# MK66MCU.net
KiCad netlist of a schematic drawn in Altium Designer
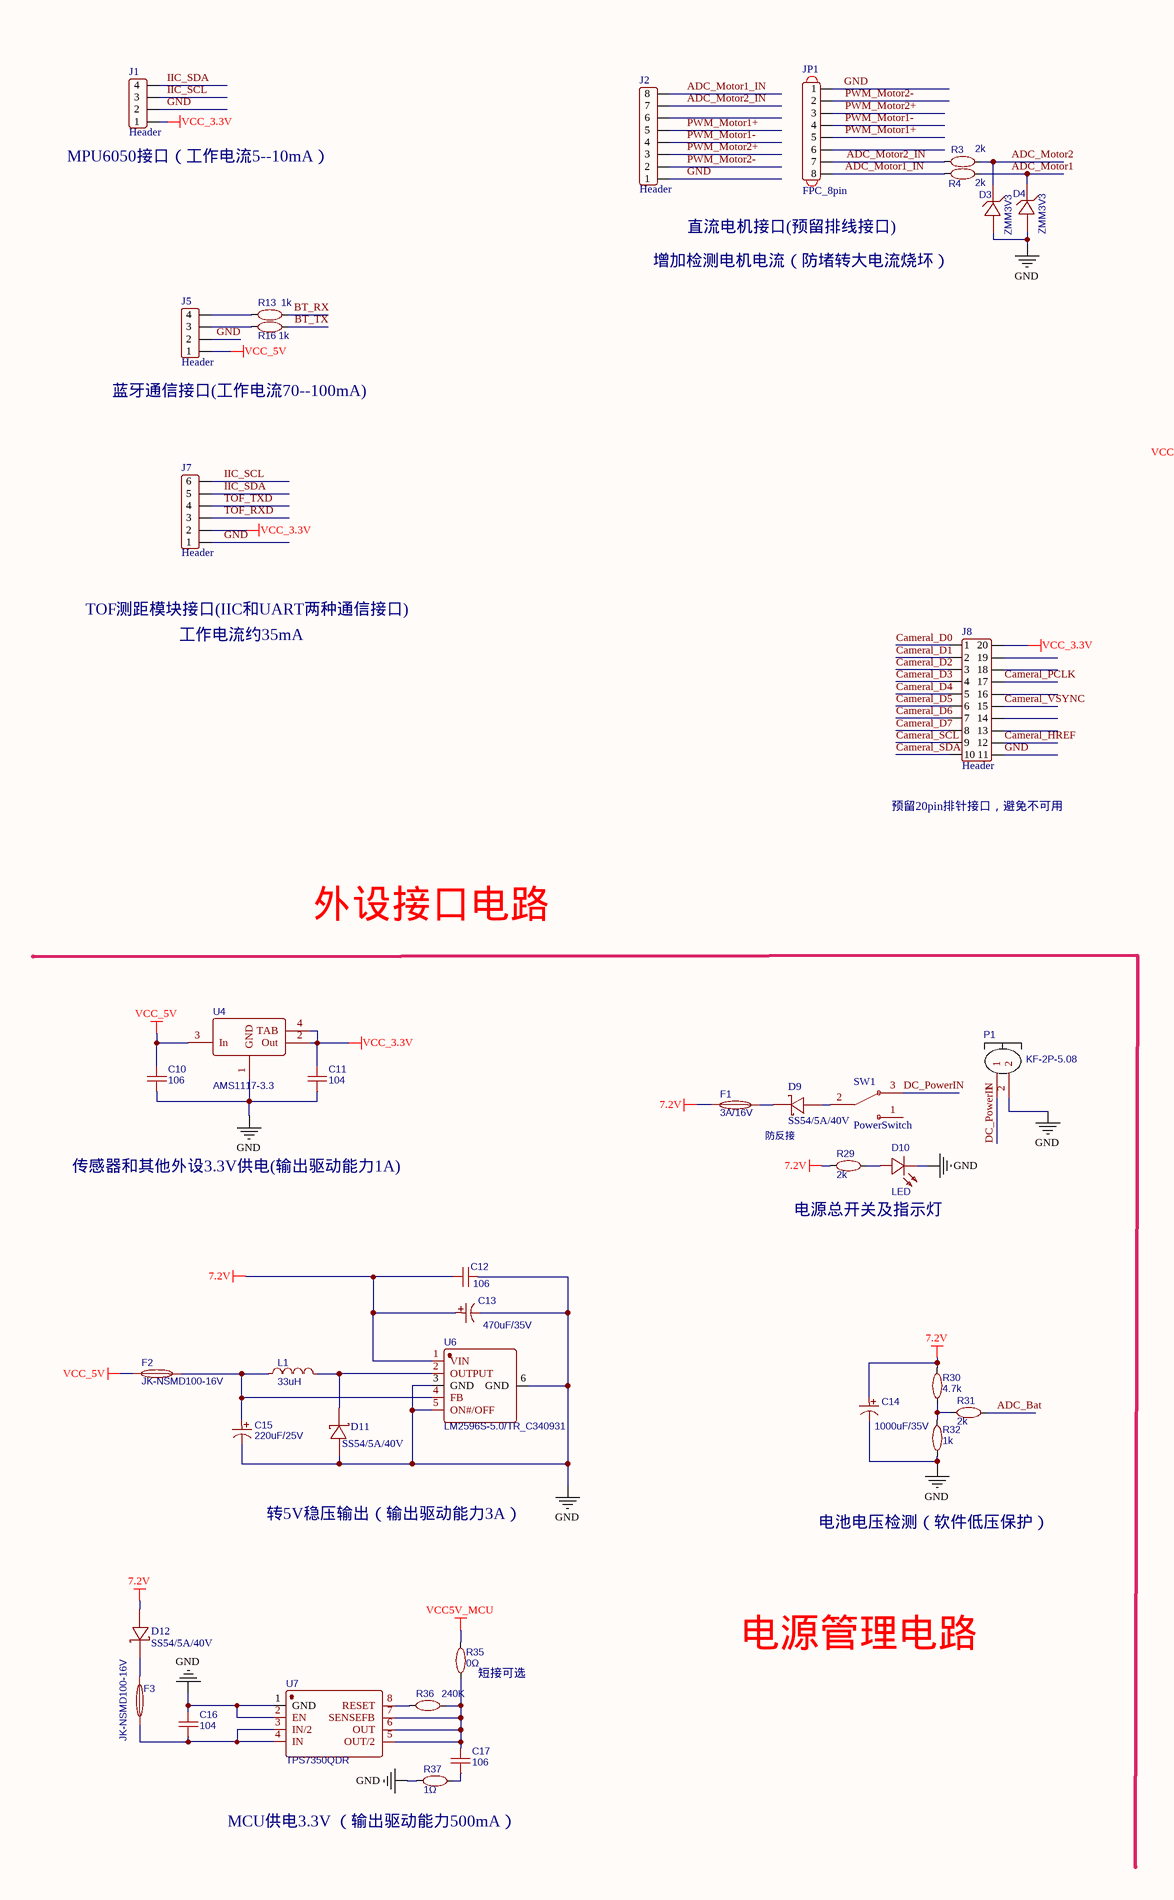
[diagram p0: MK66MCU.SchDoc, left]
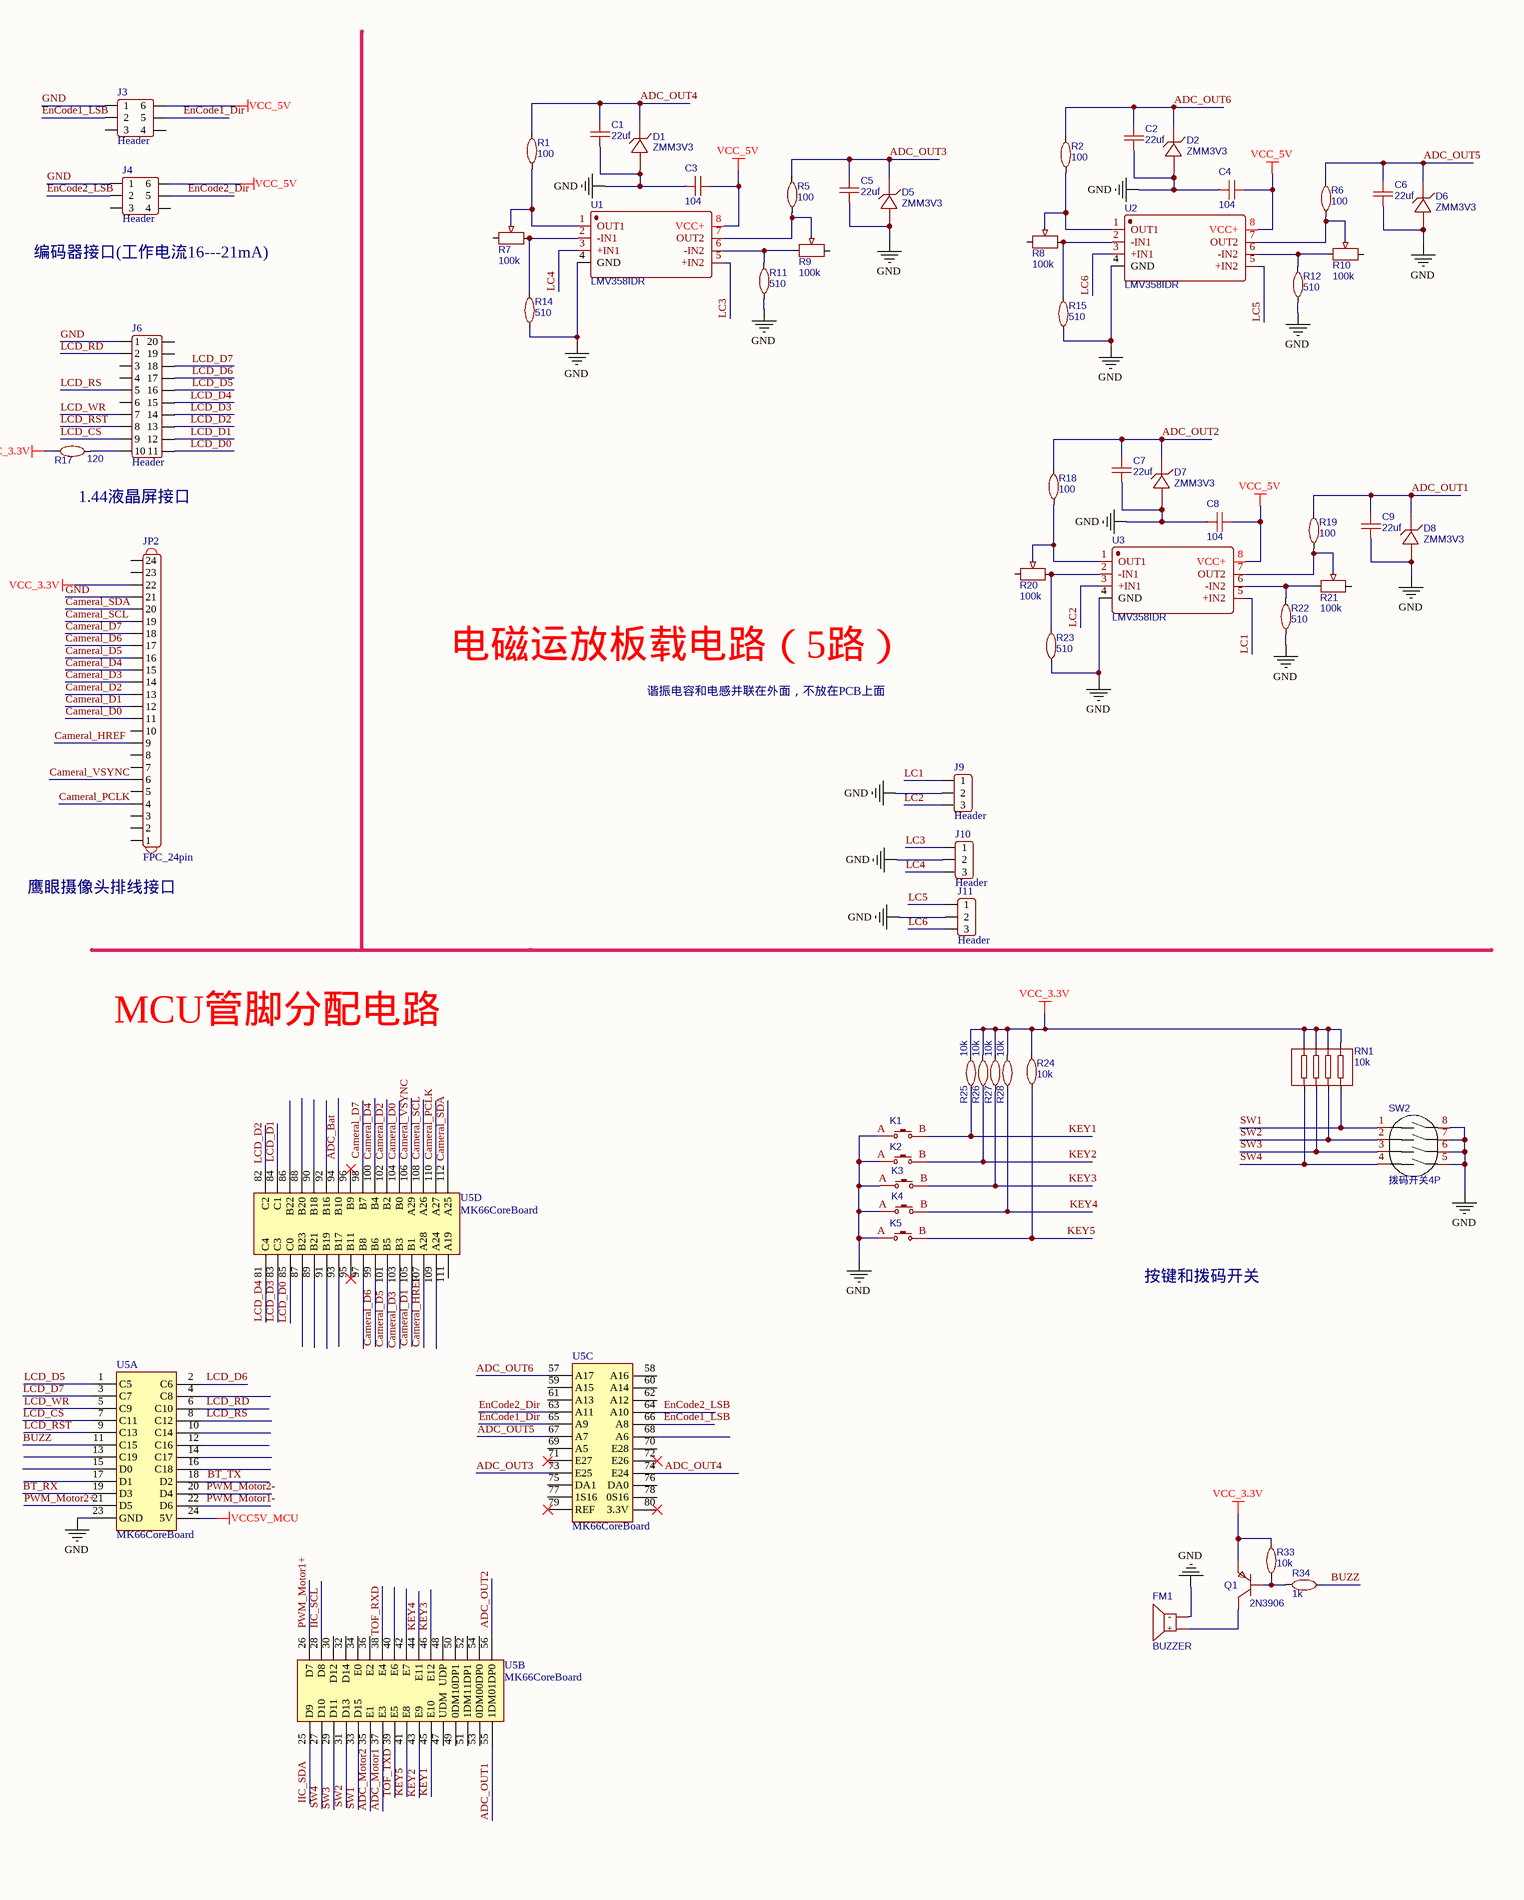
[diagram p1: MK66MCU.SchDoc, right]

(export (version "E")
  (design (tool "Eeschema 10.0.6"))
  (components
    (comp (ref "C1")
      (value "22uf")
      (footprint "CAP_0603")
      (fields
        (field (name "BOM_SUPPLIER PART") "C307348")
        (field (name "BOM_MANUFACTURER PART") "CL10B104KB8WPNC")
        (field (name "CONTRIBUTOR") "LCSC")
      )
      (libsource (lib "LTC_Library1") (part "CAP_0603"))
    )
    (comp (ref "C2")
      (value "22uf")
      (footprint "CAP_0603")
      (fields
        (field (name "BOM_SUPPLIER PART") "C307348")
        (field (name "BOM_MANUFACTURER PART") "CL10B104KB8WPNC")
        (field (name "CONTRIBUTOR") "LCSC")
      )
      (libsource (lib "LTC_Library1") (part "CAP_0603"))
    )
    (comp (ref "C3")
      (value "104")
      (footprint "CAP_0603")
      (fields
        (field (name "BOM_SUPPLIER PART") "C307348")
        (field (name "BOM_MANUFACTURER PART") "CL10B104KB8WPNC")
        (field (name "CONTRIBUTOR") "LCSC")
      )
      (libsource (lib "LTC_Library1") (part "CAP_0603"))
    )
    (comp (ref "C4")
      (value "104")
      (footprint "CAP_0603")
      (fields
        (field (name "BOM_SUPPLIER PART") "C307348")
        (field (name "BOM_MANUFACTURER PART") "CL10B104KB8WPNC")
        (field (name "CONTRIBUTOR") "LCSC")
      )
      (libsource (lib "LTC_Library1") (part "CAP_0603"))
    )
    (comp (ref "C5")
      (value "22uf")
      (footprint "CAP_0603")
      (fields
        (field (name "BOM_SUPPLIER PART") "C307348")
        (field (name "BOM_MANUFACTURER PART") "CL10B104KB8WPNC")
        (field (name "CONTRIBUTOR") "LCSC")
      )
      (libsource (lib "LTC_Library1") (part "CAP_0603"))
    )
    (comp (ref "C6")
      (value "22uf")
      (footprint "CAP_0603")
      (fields
        (field (name "BOM_SUPPLIER PART") "C307348")
        (field (name "BOM_MANUFACTURER PART") "CL10B104KB8WPNC")
        (field (name "CONTRIBUTOR") "LCSC")
      )
      (libsource (lib "LTC_Library1") (part "CAP_0603"))
    )
    (comp (ref "C7")
      (value "22uf")
      (footprint "CAP_0603")
      (fields
        (field (name "BOM_SUPPLIER PART") "C307348")
        (field (name "BOM_MANUFACTURER PART") "CL10B104KB8WPNC")
        (field (name "CONTRIBUTOR") "LCSC")
      )
      (libsource (lib "LTC_Library1") (part "CAP_0603"))
    )
    (comp (ref "C8")
      (value "104")
      (footprint "CAP_0603")
      (fields
        (field (name "BOM_SUPPLIER PART") "C307348")
        (field (name "BOM_MANUFACTURER PART") "CL10B104KB8WPNC")
        (field (name "CONTRIBUTOR") "LCSC")
      )
      (libsource (lib "LTC_Library1") (part "CAP_0603"))
    )
    (comp (ref "C9")
      (value "22uf")
      (footprint "CAP_0603")
      (fields
        (field (name "BOM_SUPPLIER PART") "C307348")
        (field (name "BOM_MANUFACTURER PART") "CL10B104KB8WPNC")
        (field (name "CONTRIBUTOR") "LCSC")
      )
      (libsource (lib "LTC_Library1") (part "CAP_0603"))
    )
    (comp (ref "C10")
      (value "106")
      (footprint "CAP_0603")
      (fields
        (field (name "BOM_SUPPLIER PART") "C307348")
        (field (name "BOM_MANUFACTURER PART") "CL10B104KB8WPNC")
        (field (name "CONTRIBUTOR") "LCSC")
      )
      (libsource (lib "LTC_Library1") (part "CAP_0603"))
    )
    (comp (ref "C11")
      (value "104")
      (footprint "CAP_0603")
      (fields
        (field (name "BOM_SUPPLIER PART") "C307348")
        (field (name "BOM_MANUFACTURER PART") "CL10B104KB8WPNC")
        (field (name "CONTRIBUTOR") "LCSC")
      )
      (libsource (lib "LTC_Library1") (part "CAP_0603"))
    )
    (comp (ref "C12")
      (value "106")
      (footprint "CAP_0603")
      (fields
        (field (name "BOM_SUPPLIER PART") "C307348")
        (field (name "BOM_MANUFACTURER PART") "CL10B104KB8WPNC")
        (field (name "CONTRIBUTOR") "LCSC")
      )
      (libsource (lib "LTC_Library1") (part "CAP_0603"))
    )
    (comp (ref "C13")
      (value "470uF/35V")
      (footprint "CAPE_SMD_F_8.4")
      (description "贴片电解电容")
      (fields
        (field (name "BOM_MANUFACTURER PART") "RVT1C221M0607")
        (field (name "BOM_SUPPLIER PART") "C72496")
      )
      (libsource (lib "") (part "CAP_E_SMD_1"))
    )
    (comp (ref "C14")
      (value "1000uF/35V")
      (footprint "CAPE_SMD_G_10.6")
      (description "贴片电解电容")
      (fields
        (field (name "BOM_MANUFACTURER PART") "RVT1C221M0607")
        (field (name "BOM_SUPPLIER PART") "C72496")
      )
      (libsource (lib "LTC_Library1") (part "CAP_E_SMD"))
    )
    (comp (ref "C15")
      (value "220uF/25V")
      (footprint "CAPE_SMD_D_6.4")
      (description "贴片电解电容")
      (fields
        (field (name "BOM_MANUFACTURER PART") "RVT1C221M0607")
        (field (name "BOM_SUPPLIER PART") "C72496")
      )
      (libsource (lib "LTC_Library1") (part "CAP_E_SMD"))
    )
    (comp (ref "C16")
      (value "104")
      (footprint "CAP_0603")
      (fields
        (field (name "BOM_SUPPLIER PART") "C307348")
        (field (name "BOM_MANUFACTURER PART") "CL10B104KB8WPNC")
        (field (name "CONTRIBUTOR") "LCSC")
      )
      (libsource (lib "LTC_Library1") (part "CAP_0603"))
    )
    (comp (ref "C17")
      (value "106")
      (footprint "CAP_0603")
      (fields
        (field (name "BOM_SUPPLIER PART") "C307348")
        (field (name "BOM_MANUFACTURER PART") "CL10B104KB8WPNC")
        (field (name "CONTRIBUTOR") "LCSC")
      )
      (libsource (lib "LTC_Library1") (part "CAP_0603"))
    )
    (comp (ref "D1")
      (value "ZMM3V3")
      (footprint "LL-34_L3.5-W1.5-RD")
      (fields (field (name "BOM_SUPPLIER PART") "C8056"))
      (libsource (lib "SmartCar_Library") (part "ZMM3V3"))
    )
    (comp (ref "D2")
      (value "ZMM3V3")
      (footprint "LL-34_L3.5-W1.5-RD")
      (fields (field (name "BOM_SUPPLIER PART") "C8056"))
      (libsource (lib "SmartCar_Library") (part "ZMM3V3"))
    )
    (comp (ref "D3")
      (value "ZMM3V3")
      (footprint "LL-34_L3.5-W1.5-RD")
      (fields (field (name "BOM_SUPPLIER PART") "C8056"))
      (libsource (lib "SmartCar_Library") (part "ZMM3V3"))
    )
    (comp (ref "D4")
      (value "ZMM3V3")
      (footprint "LL-34_L3.5-W1.5-RD")
      (fields (field (name "BOM_SUPPLIER PART") "C8056"))
      (libsource (lib "SmartCar_Library") (part "ZMM3V3"))
    )
    (comp (ref "D5")
      (value "ZMM3V3")
      (footprint "LL-34_L3.5-W1.5-RD")
      (fields (field (name "BOM_SUPPLIER PART") "C8056"))
      (libsource (lib "SmartCar_Library") (part "ZMM3V3"))
    )
    (comp (ref "D6")
      (value "ZMM3V3")
      (footprint "LL-34_L3.5-W1.5-RD")
      (fields (field (name "BOM_SUPPLIER PART") "C8056"))
      (libsource (lib "SmartCar_Library") (part "ZMM3V3"))
    )
    (comp (ref "D7")
      (value "ZMM3V3")
      (footprint "LL-34_L3.5-W1.5-RD")
      (fields (field (name "BOM_SUPPLIER PART") "C8056"))
      (libsource (lib "SmartCar_Library") (part "ZMM3V3"))
    )
    (comp (ref "D8")
      (value "ZMM3V3")
      (footprint "LL-34_L3.5-W1.5-RD")
      (fields (field (name "BOM_SUPPLIER PART") "C8056"))
      (libsource (lib "SmartCar_Library") (part "ZMM3V3"))
    )
    (comp (ref "D9")
      (value "SS54/5A/40V")
      (footprint "DO214_SMA")
      (libsource (lib "LTC_Library1") (part "SS54"))
    )
    (comp (ref "D10")
      (value "LED")
      (footprint "LED_0603_B")
      (description "发光LED")
      (fields
        (field (name "BOM_MANUFACTURER PART") "D-G080508G1")
        (field (name "BOM_SUPPLIER PART") "C107402")
        (field (name "CONTRIBUTOR") "LCSC")
      )
      (libsource (lib "LTC_Library1") (part "LED_0603"))
    )
    (comp (ref "D11")
      (value "SS54/5A/40V")
      (footprint "DO214_SMA")
      (libsource (lib "LTC_Library1") (part "SS54"))
    )
    (comp (ref "D12")
      (value "SS54/5A/40V")
      (footprint "DO214_SMA")
      (libsource (lib "LTC_Library1") (part "SS54"))
    )
    (comp (ref "F1")
      (value "3A/16V")
      (footprint "F1206")
      (fields
        (field (name "BOM_SUPPLIER PART") "C369161")
        (field (name "BOM_MANUFACTURER PART") "JK-NSMD100-16V")
        (field (name "CONTRIBUTOR") "LCSC")
      )
      (libsource (lib "SmartCar_Library") (part "JK-NSMD100-16V"))
    )
    (comp (ref "F2")
      (value "JK-NSMD100-16V")
      (footprint "F1206")
      (fields (field (name "BOM_SUPPLIER PART") "C369161") (field (name "CONTRIBUTOR") "LCSC"))
      (libsource (lib "SmartCar_Library") (part "JK-NSMD100-16V"))
    )
    (comp (ref "F3")
      (value "JK-NSMD100-16V")
      (footprint "F1206")
      (fields (field (name "BOM_SUPPLIER PART") "C369161") (field (name "CONTRIBUTOR") "LCSC"))
      (libsource (lib "SmartCar_Library") (part "JK-NSMD100-16V"))
    )
    (comp (ref "FM1")
      (value "BUZZER")
      (footprint "BUZZ-12*7.5")
      (description "蜂鸣器")
      (fields (field (name "BOM_MANUFACTURER PART") "TMB12A12") (field (name "BOM_SUPPLIER PART") "C96079"))
      (libsource (lib "LTC_Library1") (part "BUZZER"))
    )
    (comp (ref "J1")
      (value "Header")
      (footprint "Header 2.54X4")
      (libsource (lib "LTC_Library1") (part "Header 2.54_4"))
    )
    (comp (ref "J2")
      (value "Header")
      (footprint "Header 2.54X8")
      (libsource (lib "LTC_Library1") (part "Header 2.54_8"))
    )
    (comp (ref "J3")
      (value "Header")
      (footprint "Header 2.54_2X3")
      (libsource (lib "LTC_Library1") (part "Header 2.54_2X3"))
    )
    (comp (ref "J4")
      (value "Header")
      (footprint "Header 2.54_2X3")
      (libsource (lib "LTC_Library1") (part "Header 2.54_2X3"))
    )
    (comp (ref "J5")
      (value "Header")
      (footprint "Header F 2.54X4")
      (libsource (lib "LTC_Library1") (part "Header 2.54_4"))
    )
    (comp (ref "J6")
      (value "Header")
      (footprint "Header F 2.54_2x10")
      (libsource (lib "LTC_Library1") (part "Header 2.54_2X10"))
    )
    (comp (ref "J7")
      (value "Header")
      (footprint "Header 2.54X6")
      (libsource (lib "LTC_Library1") (part "Header 2.54_6"))
    )
    (comp (ref "J8")
      (value "Header")
      (footprint "Header F 2.54_2x10")
      (libsource (lib "LTC_Library1") (part "Header 2.54_2X10"))
    )
    (comp (ref "J9")
      (value "Header")
      (footprint "Header 2.54X3")
      (libsource (lib "LTC_Library1") (part "Header 2.54_3"))
    )
    (comp (ref "J10")
      (value "Header")
      (footprint "Header 2.54X3")
      (libsource (lib "LTC_Library1") (part "Header 2.54_3"))
    )
    (comp (ref "J11")
      (value "Header")
      (footprint "Header 2.54X3")
      (libsource (lib "LTC_Library1") (part "Header 2.54_3"))
    )
    (comp (ref "JP1")
      (value "FPC_8pin")
      (footprint "FPC_1.0_8P")
      (libsource (lib "LTC_Library1") (part "FPC_8pin"))
    )
    (comp (ref "JP2")
      (value "FPC_24pin")
      (footprint "FPC_0.5_24P")
      (libsource (lib "External Interface") (part "FPC_24pin"))
    )
    (comp (ref "K1")
      (value "TS-Button_2P")
      (footprint "SW_SMD_6.1*3.7")
      (description "贴片按键 3*6*2.5")
      (fields
        (field (name "BOM_SUPPLIER PART") "C455236")
        (field (name "BOM_MANUFACTURER PART") "TS-1007S-26")
        (field (name "CONTRIBUTOR") "LCSC")
      )
      (libsource (lib "LTC_Library1") (part "TS-Button_2P"))
    )
    (comp (ref "K2")
      (value "TS-Button_2P")
      (footprint "SW_SMD_6.1*3.7")
      (description "贴片按键 3*6*2.5")
      (fields
        (field (name "BOM_SUPPLIER PART") "C455236")
        (field (name "BOM_MANUFACTURER PART") "TS-1007S-26")
        (field (name "CONTRIBUTOR") "LCSC")
      )
      (libsource (lib "LTC_Library1") (part "TS-Button_2P"))
    )
    (comp (ref "K3")
      (value "TS-Button_2P")
      (footprint "SW_SMD_6.1*3.7")
      (description "贴片按键 3*6*2.5")
      (fields
        (field (name "BOM_SUPPLIER PART") "C455236")
        (field (name "BOM_MANUFACTURER PART") "TS-1007S-26")
        (field (name "CONTRIBUTOR") "LCSC")
      )
      (libsource (lib "LTC_Library1") (part "TS-Button_2P"))
    )
    (comp (ref "K4")
      (value "TS-Button_2P")
      (footprint "SW_SMD_6.1*3.7")
      (description "贴片按键 3*6*2.5")
      (fields
        (field (name "BOM_SUPPLIER PART") "C455236")
        (field (name "BOM_MANUFACTURER PART") "TS-1007S-26")
        (field (name "CONTRIBUTOR") "LCSC")
      )
      (libsource (lib "LTC_Library1") (part "TS-Button_2P"))
    )
    (comp (ref "K5")
      (value "TS-Button_2P")
      (footprint "SW_SMD_6.1*3.7")
      (description "贴片按键 3*6*2.5")
      (fields
        (field (name "BOM_SUPPLIER PART") "C455236")
        (field (name "BOM_MANUFACTURER PART") "TS-1007S-26")
        (field (name "CONTRIBUTOR") "LCSC")
      )
      (libsource (lib "LTC_Library1") (part "TS-Button_2P"))
    )
    (comp (ref "L1")
      (value "33uH")
      (footprint "IND-SMD_L8.0-W8.0")
      (fields
        (field (name "BOM_SUPPLIER PART") "C295130")
        (field (name "BOM_MANUFACTURER PART") "NLV25T-330J-EF")
        (field (name "CONTRIBUTOR") "LCSC")
      )
      (libsource (lib "SmartCar_Library") (part "Inductor"))
    )
    (comp (ref "P1")
      (value "KF-2P-5.08")
      (footprint "KF_2P-5.08")
      (description "端子2P")
      (fields
        (field (name "BOM_MANUFACTURER PART") "WJ500H-5.08-2P")
        (field (name "BOM_SUPPLIER PART") "C8478")
      )
      (libsource (lib "LTC_Library1") (part "KF-2P-5.08"))
    )
    (comp (ref "Q1")
      (value "2N3906")
      (footprint "TO_92A")
      (description "三极管PNP")
      (fields (field (name "BOM_SUPPLIER PART") "C305396") (field (name "CONTRIBUTOR") "LCSC"))
      (libsource (lib "LTC_Library1") (part "2N3906"))
    )
    (comp (ref "R1")
      (value "100")
      (footprint "RES_0603")
      (fields
        (field (name "BOM_MANUFACTURER PART") "RC0402JR-07100KL")
        (field (name "BOM_SUPPLIER PART") "C106234")
      )
      (libsource (lib "LTC_Library1") (part "RES_0603"))
    )
    (comp (ref "R2")
      (value "100")
      (footprint "RES_0603")
      (fields
        (field (name "BOM_MANUFACTURER PART") "RC0402JR-07100KL")
        (field (name "BOM_SUPPLIER PART") "C106234")
      )
      (libsource (lib "LTC_Library1") (part "RES_0603"))
    )
    (comp (ref "R3")
      (value "2k")
      (footprint "RES_0603")
      (fields
        (field (name "BOM_MANUFACTURER PART") "RC0402JR-07100KL")
        (field (name "BOM_SUPPLIER PART") "C106234")
      )
      (libsource (lib "LTC_Library1") (part "RES_0603"))
    )
    (comp (ref "R4")
      (value "2k")
      (footprint "RES_0603")
      (fields
        (field (name "BOM_MANUFACTURER PART") "RC0402JR-07100KL")
        (field (name "BOM_SUPPLIER PART") "C106234")
      )
      (libsource (lib "LTC_Library1") (part "RES_0603"))
    )
    (comp (ref "R5")
      (value "100")
      (footprint "RES_0603")
      (fields
        (field (name "BOM_MANUFACTURER PART") "RC0402JR-07100KL")
        (field (name "BOM_SUPPLIER PART") "C106234")
      )
      (libsource (lib "LTC_Library1") (part "RES_0603"))
    )
    (comp (ref "R6")
      (value "100")
      (footprint "RES_0603")
      (fields
        (field (name "BOM_MANUFACTURER PART") "RC0402JR-07100KL")
        (field (name "BOM_SUPPLIER PART") "C106234")
      )
      (libsource (lib "LTC_Library1") (part "RES_0603"))
    )
    (comp (ref "R7")
      (value "100k")
      (footprint "RES_POT-3296W")
      (description "可调电阻3296W")
      (fields
        (field (name "BOM_SUPPLIER PART") "C118963")
        (field (name "BOM_MANUFACTURER PART") "3296W-1-104")
        (field (name "CONTRIBUTOR") "LCSC")
      )
      (libsource (lib "LTC_Library1") (part "RES_POT-3296W"))
    )
    (comp (ref "R8")
      (value "100k")
      (footprint "RES_POT-3296W")
      (description "可调电阻3296W")
      (fields
        (field (name "BOM_SUPPLIER PART") "C118963")
        (field (name "BOM_MANUFACTURER PART") "3296W-1-104")
        (field (name "CONTRIBUTOR") "LCSC")
      )
      (libsource (lib "LTC_Library1") (part "RES_POT-3296W"))
    )
    (comp (ref "R9")
      (value "100k")
      (footprint "RES_POT-3296W")
      (description "可调电阻3296W")
      (fields
        (field (name "BOM_SUPPLIER PART") "C118963")
        (field (name "BOM_MANUFACTURER PART") "3296W-1-104")
        (field (name "CONTRIBUTOR") "LCSC")
      )
      (libsource (lib "LTC_Library1") (part "RES_POT-3296W"))
    )
    (comp (ref "R10")
      (value "100k")
      (footprint "RES_POT-3296W")
      (description "可调电阻3296W")
      (fields
        (field (name "BOM_SUPPLIER PART") "C118963")
        (field (name "BOM_MANUFACTURER PART") "3296W-1-104")
        (field (name "CONTRIBUTOR") "LCSC")
      )
      (libsource (lib "LTC_Library1") (part "RES_POT-3296W"))
    )
    (comp (ref "R11")
      (value "510")
      (footprint "RES_0603")
      (fields
        (field (name "BOM_MANUFACTURER PART") "RC0402JR-07100KL")
        (field (name "BOM_SUPPLIER PART") "C106234")
      )
      (libsource (lib "LTC_Library1") (part "RES_0603"))
    )
    (comp (ref "R12")
      (value "510")
      (footprint "RES_0603")
      (fields
        (field (name "BOM_MANUFACTURER PART") "RC0402JR-07100KL")
        (field (name "BOM_SUPPLIER PART") "C106234")
      )
      (libsource (lib "LTC_Library1") (part "RES_0603"))
    )
    (comp (ref "R13")
      (value "1k")
      (footprint "RES_0603")
      (fields
        (field (name "BOM_MANUFACTURER PART") "RC0402JR-07100KL")
        (field (name "BOM_SUPPLIER PART") "C106234")
      )
      (libsource (lib "LTC_Library1") (part "RES_0603"))
    )
    (comp (ref "R14")
      (value "510")
      (footprint "RES_0603")
      (fields
        (field (name "BOM_MANUFACTURER PART") "RC0402JR-07100KL")
        (field (name "BOM_SUPPLIER PART") "C106234")
      )
      (libsource (lib "LTC_Library1") (part "RES_0603"))
    )
    (comp (ref "R15")
      (value "510")
      (footprint "RES_0603")
      (fields
        (field (name "BOM_MANUFACTURER PART") "RC0402JR-07100KL")
        (field (name "BOM_SUPPLIER PART") "C106234")
      )
      (libsource (lib "LTC_Library1") (part "RES_0603"))
    )
    (comp (ref "R16")
      (value "1k")
      (footprint "RES_0603")
      (fields
        (field (name "BOM_MANUFACTURER PART") "RC0402JR-07100KL")
        (field (name "BOM_SUPPLIER PART") "C106234")
      )
      (libsource (lib "LTC_Library1") (part "RES_0603"))
    )
    (comp (ref "R17")
      (value "120")
      (footprint "RES_0603")
      (fields
        (field (name "BOM_MANUFACTURER PART") "RC0402JR-07100KL")
        (field (name "BOM_SUPPLIER PART") "C106234")
      )
      (libsource (lib "LTC_Library1") (part "RES_0603"))
    )
    (comp (ref "R18")
      (value "100")
      (footprint "RES_0603")
      (fields
        (field (name "BOM_MANUFACTURER PART") "RC0402JR-07100KL")
        (field (name "BOM_SUPPLIER PART") "C106234")
      )
      (libsource (lib "LTC_Library1") (part "RES_0603"))
    )
    (comp (ref "R19")
      (value "100")
      (footprint "RES_0603")
      (fields
        (field (name "BOM_MANUFACTURER PART") "RC0402JR-07100KL")
        (field (name "BOM_SUPPLIER PART") "C106234")
      )
      (libsource (lib "LTC_Library1") (part "RES_0603"))
    )
    (comp (ref "R20")
      (value "100k")
      (footprint "RES_POT-3296W")
      (description "可调电阻3296W")
      (fields
        (field (name "BOM_SUPPLIER PART") "C118963")
        (field (name "BOM_MANUFACTURER PART") "3296W-1-104")
        (field (name "CONTRIBUTOR") "LCSC")
      )
      (libsource (lib "LTC_Library1") (part "RES_POT-3296W"))
    )
    (comp (ref "R21")
      (value "100k")
      (footprint "RES_POT-3296W")
      (description "可调电阻3296W")
      (fields
        (field (name "BOM_SUPPLIER PART") "C118963")
        (field (name "BOM_MANUFACTURER PART") "3296W-1-104")
        (field (name "CONTRIBUTOR") "LCSC")
      )
      (libsource (lib "LTC_Library1") (part "RES_POT-3296W"))
    )
    (comp (ref "R22")
      (value "510")
      (footprint "RES_0603")
      (fields
        (field (name "BOM_MANUFACTURER PART") "RC0402JR-07100KL")
        (field (name "BOM_SUPPLIER PART") "C106234")
      )
      (libsource (lib "LTC_Library1") (part "RES_0603"))
    )
    (comp (ref "R23")
      (value "510")
      (footprint "RES_0603")
      (fields
        (field (name "BOM_MANUFACTURER PART") "RC0402JR-07100KL")
        (field (name "BOM_SUPPLIER PART") "C106234")
      )
      (libsource (lib "LTC_Library1") (part "RES_0603"))
    )
    (comp (ref "R24")
      (value "10k")
      (footprint "RES_0603")
      (fields
        (field (name "BOM_MANUFACTURER PART") "RC0402JR-07100KL")
        (field (name "BOM_SUPPLIER PART") "C106234")
      )
      (libsource (lib "LTC_Library1") (part "RES_0603"))
    )
    (comp (ref "R25")
      (value "10k")
      (footprint "RES_0603")
      (fields
        (field (name "BOM_MANUFACTURER PART") "RC0402JR-07100KL")
        (field (name "BOM_SUPPLIER PART") "C106234")
      )
      (libsource (lib "LTC_Library1") (part "RES_0603"))
    )
    (comp (ref "R26")
      (value "10k")
      (footprint "RES_0603")
      (fields
        (field (name "BOM_MANUFACTURER PART") "RC0402JR-07100KL")
        (field (name "BOM_SUPPLIER PART") "C106234")
      )
      (libsource (lib "LTC_Library1") (part "RES_0603"))
    )
    (comp (ref "R27")
      (value "10k")
      (footprint "RES_0603")
      (fields
        (field (name "BOM_MANUFACTURER PART") "RC0402JR-07100KL")
        (field (name "BOM_SUPPLIER PART") "C106234")
      )
      (libsource (lib "LTC_Library1") (part "RES_0603"))
    )
    (comp (ref "R28")
      (value "10k")
      (footprint "RES_0603")
      (fields
        (field (name "BOM_MANUFACTURER PART") "RC0402JR-07100KL")
        (field (name "BOM_SUPPLIER PART") "C106234")
      )
      (libsource (lib "LTC_Library1") (part "RES_0603"))
    )
    (comp (ref "R29")
      (value "2k")
      (footprint "RES_0603")
      (fields
        (field (name "BOM_MANUFACTURER PART") "RC0402JR-07100KL")
        (field (name "BOM_SUPPLIER PART") "C106234")
      )
      (libsource (lib "LTC_Library1") (part "RES_0603"))
    )
    (comp (ref "R30")
      (value "4.7k")
      (footprint "RES_0603")
      (fields
        (field (name "BOM_MANUFACTURER PART") "RC0402JR-07100KL")
        (field (name "BOM_SUPPLIER PART") "C106234")
      )
      (libsource (lib "LTC_Library1") (part "RES_0603"))
    )
    (comp (ref "R31")
      (value "2k")
      (footprint "RES_0603")
      (fields
        (field (name "BOM_MANUFACTURER PART") "RC0402JR-07100KL")
        (field (name "BOM_SUPPLIER PART") "C106234")
      )
      (libsource (lib "LTC_Library1") (part "RES_0603"))
    )
    (comp (ref "R32")
      (value "1k")
      (footprint "RES_0603")
      (fields
        (field (name "BOM_MANUFACTURER PART") "RC0402JR-07100KL")
        (field (name "BOM_SUPPLIER PART") "C106234")
      )
      (libsource (lib "LTC_Library1") (part "RES_0603"))
    )
    (comp (ref "R33")
      (value "10k")
      (footprint "RES_0603")
      (fields
        (field (name "BOM_MANUFACTURER PART") "RC0402JR-07100KL")
        (field (name "BOM_SUPPLIER PART") "C106234")
      )
      (libsource (lib "LTC_Library1") (part "RES_0603"))
    )
    (comp (ref "R34")
      (value "1k")
      (footprint "RES_0603")
      (fields
        (field (name "BOM_MANUFACTURER PART") "RC0402JR-07100KL")
        (field (name "BOM_SUPPLIER PART") "C106234")
      )
      (libsource (lib "LTC_Library1") (part "RES_0603"))
    )
    (comp (ref "R35")
      (value "0Ω")
      (footprint "RES_0603")
      (fields
        (field (name "BOM_MANUFACTURER PART") "RC0402JR-07100KL")
        (field (name "BOM_SUPPLIER PART") "C106234")
      )
      (libsource (lib "LTC_Library1") (part "RES_0603"))
    )
    (comp (ref "R36")
      (value "240K")
      (footprint "RES_0603")
      (fields
        (field (name "BOM_MANUFACTURER PART") "RC0402JR-07100KL")
        (field (name "BOM_SUPPLIER PART") "C106234")
      )
      (libsource (lib "LTC_Library1") (part "RES_0603"))
    )
    (comp (ref "R37")
      (value "1Ω")
      (footprint "RES_0603")
      (fields
        (field (name "BOM_MANUFACTURER PART") "RC0402JR-07100KL")
        (field (name "BOM_SUPPLIER PART") "C106234")
      )
      (libsource (lib "LTC_Library1") (part "RES_0603"))
    )
    (comp (ref "RN1")
      (value "10k")
      (footprint "RES-ARRAY-SMD_0603-8P-L3.2-W1.6-BL")
      (fields
        (field (name "BOM_MANUFACTURER PART") "YC164-JR-0710KL")
        (field (name "BOM_SUPPLIER PART") "C107374")
      )
      (libsource (lib "SmartCar_Library") (part "RESW4"))
    )
    (comp (ref "SW1")
      (value "PowerSwitch")
      (footprint "SW-TH_K3-1260D-K1")
      (libsource (lib "SmartCar_Library") (part "PowerSwitch"))
    )
    (comp (ref "SW2")
      (value "拨码开关4P")
      (footprint "VDG/S-04HG-R")
      (description "DIP_4PX2*2.54")
      (fields
        (field (name "BOM_MANUFACTURER PART") "VDG/S-04HG-R")
        (field (name "BOM_SUPPLIER PART") "C15781")
      )
      (libsource (lib "LTC_Library1") (part "拨码开关4P"))
    )
    (comp (ref "U1")
      (value "LMV358IDR")
      (footprint "SOIC-8_150MIL")
      (fields (field (name "BOM_SUPPLIER PART") "C63813"))
      (libsource (lib "LTC_Library1") (part "LMV358IDR"))
    )
    (comp (ref "U2")
      (value "LMV358IDR")
      (footprint "SOIC-8_150MIL")
      (fields (field (name "BOM_SUPPLIER PART") "C63813"))
      (libsource (lib "LTC_Library1") (part "LMV358IDR"))
    )
    (comp (ref "U3")
      (value "LMV358IDR")
      (footprint "SOIC-8_150MIL")
      (fields (field (name "BOM_SUPPLIER PART") "C63813"))
      (libsource (lib "LTC_Library1") (part "LMV358IDR"))
    )
    (comp (ref "U4")
      (value "AMS1117-3.3")
      (footprint "SOT-223_3")
      (fields (field (name "BOM_SUPPLIER PART") "C165482") (field (name "CONTRIBUTOR") "LCSC"))
      (libsource (lib "LTC_Library1") (part "AMS1117-3.3"))
    )
    (comp (ref "U5")
      (value "MK66CoreBoard")
      (footprint "MK66_MCU")
      (libsource (lib "") (part "MK66CoreBoard_1"))
    )
    (comp (ref "U6")
      (value "LM2596S-5.0/TR_C340931")
      (footprint "TO-263_5")
      (fields
        (field (name "BOM_SUPPLIER PART") "C340931")
        (field (name "BOM_MANUFACTURER PART") "LM2596S-5.0/TR")
        (field (name "CONTRIBUTOR") "LCSC")
      )
      (libsource (lib "LTC_Library1") (part "LM2596S-5.0/TR_C340931"))
    )
    (comp (ref "U7")
      (value "TPS7350QDR")
      (footprint "SOIC-8_150MIL")
      (fields (field (name "BOM_MANUFACTURER PART") "TPS7333QDR") (field (name "BOM_SUPPLIER PART") "C23791"))
      (libsource (lib "LTC_Library1") (part "TPS7350QDR"))
    )
  )
  (nets
    (net (code "1") (name "/ADC_Bat") (class "Default")
      (node (ref "R31") (pin "2") (pinfunction "2_2") (pintype "passive"))
      (node (ref "U5") (pin "94") (pinfunction "B10_94") (pintype "passive"))
    )
    (net (code "2") (name "/ADC_Motor1") (class "Default")
      (node (ref "D4") (pin "1") (pinfunction "C_1") (pintype "passive"))
      (node (ref "R4") (pin "1") (pinfunction "1_1") (pintype "passive"))
      (node (ref "U5") (pin "37") (pinfunction "E3_37") (pintype "passive"))
    )
    (net (code "3") (name "/ADC_Motor1_IN") (class "Default")
      (node (ref "J2") (pin "8") (pinfunction "8_8") (pintype "passive"))
      (node (ref "JP1") (pin "8") (pinfunction "8_8") (pintype "passive"))
      (node (ref "R4") (pin "2") (pinfunction "2_2") (pintype "passive"))
    )
    (net (code "4") (name "/ADC_Motor2") (class "Default")
      (node (ref "D3") (pin "1") (pinfunction "C_1") (pintype "passive"))
      (node (ref "R3") (pin "1") (pinfunction "1_1") (pintype "passive"))
      (node (ref "U5") (pin "35") (pinfunction "E1_35") (pintype "passive"))
    )
    (net (code "5") (name "/ADC_Motor2_IN") (class "Default")
      (node (ref "J2") (pin "7") (pinfunction "7_7") (pintype "passive"))
      (node (ref "JP1") (pin "7") (pinfunction "7_7") (pintype "passive"))
      (node (ref "R3") (pin "2") (pinfunction "2_2") (pintype "passive"))
    )
    (net (code "6") (name "/ADC_OUT1") (class "Default")
      (node (ref "C9") (pin "1") (pinfunction "1_1") (pintype "passive"))
      (node (ref "D8") (pin "1") (pinfunction "C_1") (pintype "passive"))
      (node (ref "R19") (pin "1") (pinfunction "1_1") (pintype "passive"))
      (node (ref "U5") (pin "55") (pinfunction "1DM0_55") (pintype "passive"))
    )
    (net (code "7") (name "/ADC_OUT2") (class "Default")
      (node (ref "C7") (pin "1") (pinfunction "1_1") (pintype "passive"))
      (node (ref "D7") (pin "1") (pinfunction "C_1") (pintype "passive"))
      (node (ref "R18") (pin "1") (pinfunction "1_1") (pintype "passive"))
      (node (ref "U5") (pin "56") (pinfunction "1DP0_56") (pintype "passive"))
    )
    (net (code "8") (name "/ADC_OUT3") (class "Default")
      (node (ref "C5") (pin "1") (pinfunction "1_1") (pintype "passive"))
      (node (ref "D5") (pin "1") (pinfunction "C_1") (pintype "passive"))
      (node (ref "R5") (pin "1") (pinfunction "1_1") (pintype "passive"))
      (node (ref "U5") (pin "73") (pinfunction "E25_73") (pintype "passive"))
    )
    (net (code "9") (name "/ADC_OUT4") (class "Default")
      (node (ref "C1") (pin "1") (pinfunction "1_1") (pintype "passive"))
      (node (ref "D1") (pin "1") (pinfunction "C_1") (pintype "passive"))
      (node (ref "R1") (pin "1") (pinfunction "1_1") (pintype "passive"))
      (node (ref "U5") (pin "74") (pinfunction "E24_74") (pintype "passive"))
    )
    (net (code "10") (name "/ADC_OUT5") (class "Default")
      (node (ref "C6") (pin "1") (pinfunction "1_1") (pintype "passive"))
      (node (ref "D6") (pin "1") (pinfunction "C_1") (pintype "passive"))
      (node (ref "R6") (pin "1") (pinfunction "1_1") (pintype "passive"))
      (node (ref "U5") (pin "67") (pinfunction "A7_67") (pintype "passive"))
    )
    (net (code "11") (name "/ADC_OUT6") (class "Default")
      (node (ref "C2") (pin "1") (pinfunction "1_1") (pintype "passive"))
      (node (ref "D2") (pin "1") (pinfunction "C_1") (pintype "passive"))
      (node (ref "R2") (pin "1") (pinfunction "1_1") (pintype "passive"))
      (node (ref "U5") (pin "57") (pinfunction "A17_57") (pintype "passive"))
    )
    (net (code "12") (name "/BT_RX") (class "Default")
      (node (ref "R13") (pin "1") (pinfunction "1_1") (pintype "passive"))
      (node (ref "U5") (pin "19") (pinfunction "D3_19") (pintype "passive"))
    )
    (net (code "13") (name "/BT_TX") (class "Default")
      (node (ref "R16") (pin "1") (pinfunction "1_1") (pintype "passive"))
      (node (ref "U5") (pin "18") (pinfunction "D2_18") (pintype "passive"))
    )
    (net (code "14") (name "/BUZZ") (class "Default")
      (node (ref "R34") (pin "1") (pinfunction "1_1") (pintype "passive"))
      (node (ref "U5") (pin "11") (pinfunction "C15_11") (pintype "passive"))
    )
    (net (code "15") (name "/Cameral_D0") (class "Default")
      (node (ref "J8") (pin "1") (pinfunction "1_1") (pintype "passive"))
      (node (ref "JP2") (pin "11") (pinfunction "11_11") (pintype "passive"))
      (node (ref "U5") (pin "104") (pinfunction "B0_104") (pintype "passive"))
    )
    (net (code "16") (name "/Cameral_D1") (class "Default")
      (node (ref "J8") (pin "2") (pinfunction "2_2") (pintype "passive"))
      (node (ref "JP2") (pin "12") (pinfunction "12_12") (pintype "passive"))
      (node (ref "U5") (pin "105") (pinfunction "B1_105") (pintype "passive"))
    )
    (net (code "17") (name "/Cameral_D2") (class "Default")
      (node (ref "J8") (pin "3") (pinfunction "3_3") (pintype "passive"))
      (node (ref "JP2") (pin "13") (pinfunction "13_13") (pintype "passive"))
      (node (ref "U5") (pin "102") (pinfunction "B2_102") (pintype "passive"))
    )
    (net (code "18") (name "/Cameral_D3") (class "Default")
      (node (ref "J8") (pin "4") (pinfunction "4_4") (pintype "passive"))
      (node (ref "JP2") (pin "14") (pinfunction "14_14") (pintype "passive"))
      (node (ref "U5") (pin "103") (pinfunction "B3_103") (pintype "passive"))
    )
    (net (code "19") (name "/Cameral_D4") (class "Default")
      (node (ref "J8") (pin "5") (pinfunction "5_5") (pintype "passive"))
      (node (ref "JP2") (pin "15") (pinfunction "15_15") (pintype "passive"))
      (node (ref "U5") (pin "100") (pinfunction "B4_100") (pintype "passive"))
    )
    (net (code "20") (name "/Cameral_D5") (class "Default")
      (node (ref "J8") (pin "6") (pinfunction "6_6") (pintype "passive"))
      (node (ref "JP2") (pin "16") (pinfunction "16_16") (pintype "passive"))
      (node (ref "U5") (pin "101") (pinfunction "B5_101") (pintype "passive"))
    )
    (net (code "21") (name "/Cameral_D6") (class "Default")
      (node (ref "J8") (pin "7") (pinfunction "7_7") (pintype "passive"))
      (node (ref "JP2") (pin "17") (pinfunction "17_17") (pintype "passive"))
      (node (ref "U5") (pin "99") (pinfunction "B6_99") (pintype "passive"))
    )
    (net (code "22") (name "/Cameral_D7") (class "Default")
      (node (ref "J8") (pin "8") (pinfunction "8_8") (pintype "passive"))
      (node (ref "JP2") (pin "18") (pinfunction "18_18") (pintype "passive"))
      (node (ref "U5") (pin "98") (pinfunction "B7_98") (pintype "passive"))
    )
    (net (code "23") (name "/Cameral_HREF") (class "Default")
      (node (ref "J8") (pin "12") (pinfunction "12_12") (pintype "passive"))
      (node (ref "JP2") (pin "9") (pinfunction "9_9") (pintype "passive"))
      (node (ref "U5") (pin "107") (pinfunction "A28_107") (pintype "passive"))
    )
    (net (code "24") (name "/Cameral_PCLK") (class "Default")
      (node (ref "J8") (pin "17") (pinfunction "17_17") (pintype "passive"))
      (node (ref "JP2") (pin "4") (pinfunction "4_4") (pintype "passive"))
      (node (ref "U5") (pin "110") (pinfunction "A27_110") (pintype "passive"))
    )
    (net (code "25") (name "/Cameral_SCL") (class "Default")
      (node (ref "J8") (pin "9") (pinfunction "9_9") (pintype "passive"))
      (node (ref "JP2") (pin "19") (pinfunction "19_19") (pintype "passive"))
      (node (ref "U5") (pin "108") (pinfunction "A26_108") (pintype "passive"))
    )
    (net (code "26") (name "/Cameral_SDA") (class "Default")
      (node (ref "J8") (pin "10") (pinfunction "10_10") (pintype "passive"))
      (node (ref "JP2") (pin "20") (pinfunction "20_20") (pintype "passive"))
      (node (ref "U5") (pin "112") (pinfunction "A25_112") (pintype "passive"))
    )
    (net (code "27") (name "/Cameral_VSYNC") (class "Default")
      (node (ref "J8") (pin "15") (pinfunction "15_15") (pintype "passive"))
      (node (ref "JP2") (pin "6") (pinfunction "6_6") (pintype "passive"))
      (node (ref "U5") (pin "106") (pinfunction "A29_106") (pintype "passive"))
    )
    (net (code "28") (name "/DC_PowerIN") (class "Default")
      (node (ref "P1") (pin "1") (pinfunction "1_1") (pintype "passive"))
      (node (ref "SW1") (pin "3") (pinfunction "NC_3") (pintype "passive"))
    )
    (net (code "29") (name "/EnCode1_Dir") (class "Default")
      (node (ref "J3") (pin "5") (pinfunction "5_5") (pintype "passive"))
      (node (ref "U5") (pin "65") (pinfunction "A9_65") (pintype "passive"))
    )
    (net (code "30") (name "/EnCode1_LSB") (class "Default")
      (node (ref "J3") (pin "2") (pinfunction "2_2") (pintype "passive"))
      (node (ref "U5") (pin "66") (pinfunction "A8_66") (pintype "passive"))
    )
    (net (code "31") (name "/EnCode2_Dir") (class "Default")
      (node (ref "J4") (pin "5") (pinfunction "5_5") (pintype "passive"))
      (node (ref "U5") (pin "63") (pinfunction "A11_63") (pintype "passive"))
    )
    (net (code "32") (name "/EnCode2_LSB") (class "Default")
      (node (ref "J4") (pin "2") (pinfunction "2_2") (pintype "passive"))
      (node (ref "U5") (pin "64") (pinfunction "A10_64") (pintype "passive"))
    )
    (net (code "33") (name "/IIC_SCL") (class "Default")
      (node (ref "J1") (pin "3") (pinfunction "3_3") (pintype "passive"))
      (node (ref "J7") (pin "6") (pinfunction "6_6") (pintype "passive"))
      (node (ref "U5") (pin "28") (pinfunction "D8_28") (pintype "passive"))
    )
    (net (code "34") (name "/IIC_SDA") (class "Default")
      (node (ref "J1") (pin "4") (pinfunction "4_4") (pintype "passive"))
      (node (ref "J7") (pin "5") (pinfunction "5_5") (pintype "passive"))
      (node (ref "U5") (pin "25") (pinfunction "D9_25") (pintype "passive"))
    )
    (net (code "35") (name "/KEY1") (class "Default")
      (node (ref "K1") (pin "B") (pinfunction "B_B") (pintype "passive"))
      (node (ref "R25") (pin "1") (pinfunction "1_1") (pintype "passive"))
      (node (ref "U5") (pin "45") (pinfunction "E10_45") (pintype "passive"))
    )
    (net (code "36") (name "/KEY2") (class "Default")
      (node (ref "K2") (pin "B") (pinfunction "B_B") (pintype "passive"))
      (node (ref "R26") (pin "1") (pinfunction "1_1") (pintype "passive"))
      (node (ref "U5") (pin "43") (pinfunction "E9_43") (pintype "passive"))
    )
    (net (code "37") (name "/KEY3") (class "Default")
      (node (ref "K3") (pin "B") (pinfunction "B_B") (pintype "passive"))
      (node (ref "R27") (pin "1") (pinfunction "1_1") (pintype "passive"))
      (node (ref "U5") (pin "46") (pinfunction "E12_46") (pintype "passive"))
    )
    (net (code "38") (name "/KEY4") (class "Default")
      (node (ref "K4") (pin "B") (pinfunction "B_B") (pintype "passive"))
      (node (ref "R28") (pin "1") (pinfunction "1_1") (pintype "passive"))
      (node (ref "U5") (pin "44") (pinfunction "E11_44") (pintype "passive"))
    )
    (net (code "39") (name "/KEY5") (class "Default")
      (node (ref "K5") (pin "B") (pinfunction "B_B") (pintype "passive"))
      (node (ref "R24") (pin "1") (pinfunction "1_1") (pintype "passive"))
      (node (ref "U5") (pin "41") (pinfunction "E8_41") (pintype "passive"))
    )
    (net (code "40") (name "/LC1") (class "Default")
      (node (ref "J9") (pin "1") (pinfunction "1_1") (pintype "passive"))
      (node (ref "U3") (pin "5") (pinfunction "+IN2_5") (pintype "passive"))
    )
    (net (code "41") (name "/LC2") (class "Default")
      (node (ref "J9") (pin "3") (pinfunction "3_3") (pintype "passive"))
      (node (ref "U3") (pin "3") (pinfunction "+IN1_3") (pintype "passive"))
    )
    (net (code "42") (name "/LC3") (class "Default")
      (node (ref "J10") (pin "1") (pinfunction "1_1") (pintype "passive"))
      (node (ref "U1") (pin "5") (pinfunction "+IN2_5") (pintype "passive"))
    )
    (net (code "43") (name "/LC4") (class "Default")
      (node (ref "J10") (pin "3") (pinfunction "3_3") (pintype "passive"))
      (node (ref "U1") (pin "3") (pinfunction "+IN1_3") (pintype "passive"))
    )
    (net (code "44") (name "/LC5") (class "Default")
      (node (ref "J11") (pin "1") (pinfunction "1_1") (pintype "passive"))
      (node (ref "U2") (pin "5") (pinfunction "+IN2_5") (pintype "passive"))
    )
    (net (code "45") (name "/LC6") (class "Default")
      (node (ref "J11") (pin "3") (pinfunction "3_3") (pintype "passive"))
      (node (ref "U2") (pin "3") (pinfunction "+IN1_3") (pintype "passive"))
    )
    (net (code "46") (name "/LCD_CS") (class "Default")
      (node (ref "J6") (pin "9") (pinfunction "9_9") (pintype "passive"))
      (node (ref "U5") (pin "7") (pinfunction "C11_7") (pintype "passive"))
    )
    (net (code "47") (name "/LCD_D0") (class "Default")
      (node (ref "J6") (pin "11") (pinfunction "11_11") (pintype "passive"))
      (node (ref "U5") (pin "85") (pinfunction "C0_85") (pintype "passive"))
    )
    (net (code "48") (name "/LCD_D1") (class "Default")
      (node (ref "J6") (pin "12") (pinfunction "12_12") (pintype "passive"))
      (node (ref "U5") (pin "84") (pinfunction "C1_84") (pintype "passive"))
    )
    (net (code "49") (name "/LCD_D2") (class "Default")
      (node (ref "J6") (pin "13") (pinfunction "13_13") (pintype "passive"))
      (node (ref "U5") (pin "82") (pinfunction "C2_82") (pintype "passive"))
    )
    (net (code "50") (name "/LCD_D3") (class "Default")
      (node (ref "J6") (pin "14") (pinfunction "14_14") (pintype "passive"))
      (node (ref "U5") (pin "83") (pinfunction "C3_83") (pintype "passive"))
    )
    (net (code "51") (name "/LCD_D4") (class "Default")
      (node (ref "J6") (pin "15") (pinfunction "15_15") (pintype "passive"))
      (node (ref "U5") (pin "81") (pinfunction "C4_81") (pintype "passive"))
    )
    (net (code "52") (name "/LCD_D5") (class "Default")
      (node (ref "J6") (pin "16") (pinfunction "16_16") (pintype "passive"))
      (node (ref "U5") (pin "1") (pinfunction "C5_1") (pintype "passive"))
    )
    (net (code "53") (name "/LCD_D6") (class "Default")
      (node (ref "J6") (pin "17") (pinfunction "17_17") (pintype "passive"))
      (node (ref "U5") (pin "2") (pinfunction "C6_2") (pintype "passive"))
    )
    (net (code "54") (name "/LCD_D7") (class "Default")
      (node (ref "J6") (pin "18") (pinfunction "18_18") (pintype "passive"))
      (node (ref "U5") (pin "3") (pinfunction "C7_3") (pintype "passive"))
    )
    (net (code "55") (name "/LCD_RD") (class "Default")
      (node (ref "J6") (pin "2") (pinfunction "2_2") (pintype "passive"))
      (node (ref "U5") (pin "6") (pinfunction "C10_6") (pintype "passive"))
    )
    (net (code "56") (name "/LCD_RS") (class "Default")
      (node (ref "J6") (pin "5") (pinfunction "5_5") (pintype "passive"))
      (node (ref "U5") (pin "8") (pinfunction "C12_8") (pintype "passive"))
    )
    (net (code "57") (name "/LCD_RST") (class "Default")
      (node (ref "J6") (pin "8") (pinfunction "8_8") (pintype "passive"))
      (node (ref "U5") (pin "9") (pinfunction "C13_9") (pintype "passive"))
    )
    (net (code "58") (name "/LCD_WR") (class "Default")
      (node (ref "J6") (pin "7") (pinfunction "7_7") (pintype "passive"))
      (node (ref "U5") (pin "5") (pinfunction "C9_5") (pintype "passive"))
    )
    (net (code "59") (name "/PWM_Motor1+") (class "Default")
      (node (ref "J2") (pin "5") (pinfunction "5_5") (pintype "passive"))
      (node (ref "JP1") (pin "5") (pinfunction "5_5") (pintype "passive"))
      (node (ref "U5") (pin "26") (pinfunction "D7_26") (pintype "passive"))
    )
    (net (code "60") (name "/PWM_Motor1-") (class "Default")
      (node (ref "J2") (pin "4") (pinfunction "4_4") (pintype "passive"))
      (node (ref "JP1") (pin "4") (pinfunction "4_4") (pintype "passive"))
      (node (ref "U5") (pin "22") (pinfunction "D6_22") (pintype "passive"))
    )
    (net (code "61") (name "/PWM_Motor2+") (class "Default")
      (node (ref "J2") (pin "3") (pinfunction "3_3") (pintype "passive"))
      (node (ref "JP1") (pin "3") (pinfunction "3_3") (pintype "passive"))
      (node (ref "U5") (pin "21") (pinfunction "D5_21") (pintype "passive"))
    )
    (net (code "62") (name "/PWM_Motor2-") (class "Default")
      (node (ref "J2") (pin "2") (pinfunction "2_2") (pintype "passive"))
      (node (ref "JP1") (pin "2") (pinfunction "2_2") (pintype "passive"))
      (node (ref "U5") (pin "20") (pinfunction "D4_20") (pintype "passive"))
    )
    (net (code "63") (name "/SW1") (class "Default")
      (node (ref "RN1") (pin "4") (pinfunction "4_4") (pintype "passive"))
      (node (ref "SW2") (pin "1") (pinfunction "1_1") (pintype "passive"))
      (node (ref "U5") (pin "33") (pinfunction "D15_33") (pintype "passive"))
    )
    (net (code "64") (name "/SW2") (class "Default")
      (node (ref "RN1") (pin "3") (pinfunction "3_3") (pintype "passive"))
      (node (ref "SW2") (pin "2") (pinfunction "2_2") (pintype "passive"))
      (node (ref "U5") (pin "31") (pinfunction "D13_31") (pintype "passive"))
    )
    (net (code "65") (name "/SW3") (class "Default")
      (node (ref "RN1") (pin "2") (pinfunction "2_2") (pintype "passive"))
      (node (ref "SW2") (pin "3") (pinfunction "3_3") (pintype "passive"))
      (node (ref "U5") (pin "29") (pinfunction "D11_29") (pintype "passive"))
    )
    (net (code "66") (name "/SW4") (class "Default")
      (node (ref "RN1") (pin "1") (pinfunction "1_1") (pintype "passive"))
      (node (ref "SW2") (pin "4") (pinfunction "4_4") (pintype "passive"))
      (node (ref "U5") (pin "27") (pinfunction "D10_27") (pintype "passive"))
    )
    (net (code "67") (name "/TOF_RXD") (class "Default")
      (node (ref "J7") (pin "3") (pinfunction "3_3") (pintype "passive"))
      (node (ref "U5") (pin "38") (pinfunction "E4_38") (pintype "passive"))
    )
    (net (code "68") (name "/TOF_TXD") (class "Default")
      (node (ref "J7") (pin "4") (pinfunction "4_4") (pintype "passive"))
      (node (ref "U5") (pin "39") (pinfunction "E5_39") (pintype "passive"))
    )
    (net (code "69") (name "7.2V") (class "Default")
      (node (ref "C12") (pin "1") (pinfunction "1_1") (pintype "passive"))
      (node (ref "C13") (pin "1") (pinfunction "1_1") (pintype "passive"))
      (node (ref "C14") (pin "1") (pinfunction "1_1") (pintype "passive"))
      (node (ref "D12") (pin "1") (pinfunction "A_1") (pintype "passive"))
      (node (ref "F1") (pin "2") (pinfunction "2_2") (pintype "passive"))
      (node (ref "R29") (pin "2") (pinfunction "2_2") (pintype "passive"))
      (node (ref "R30") (pin "1") (pinfunction "1_1") (pintype "passive"))
      (node (ref "U6") (pin "1") (pinfunction "VIN_1") (pintype "passive"))
    )
    (net (code "70") (name "GND") (class "Default")
      (node (ref "C1") (pin "2") (pinfunction "2_2") (pintype "passive"))
      (node (ref "C10") (pin "2") (pinfunction "2_2") (pintype "passive"))
      (node (ref "C11") (pin "2") (pinfunction "2_2") (pintype "passive"))
      (node (ref "C12") (pin "2") (pinfunction "2_2") (pintype "passive"))
      (node (ref "C13") (pin "2") (pinfunction "2_2") (pintype "passive"))
      (node (ref "C14") (pin "2") (pinfunction "2_2") (pintype "passive"))
      (node (ref "C15") (pin "2") (pinfunction "2_2") (pintype "passive"))
      (node (ref "C16") (pin "1") (pinfunction "1_1") (pintype "passive"))
      (node (ref "C2") (pin "2") (pinfunction "2_2") (pintype "passive"))
      (node (ref "C3") (pin "2") (pinfunction "2_2") (pintype "passive"))
      (node (ref "C4") (pin "2") (pinfunction "2_2") (pintype "passive"))
      (node (ref "C5") (pin "2") (pinfunction "2_2") (pintype "passive"))
      (node (ref "C6") (pin "2") (pinfunction "2_2") (pintype "passive"))
      (node (ref "C7") (pin "2") (pinfunction "2_2") (pintype "passive"))
      (node (ref "C8") (pin "2") (pinfunction "2_2") (pintype "passive"))
      (node (ref "C9") (pin "2") (pinfunction "2_2") (pintype "passive"))
      (node (ref "D1") (pin "2") (pinfunction "A_2") (pintype "passive"))
      (node (ref "D10") (pin "C") (pinfunction "C_C") (pintype "passive"))
      (node (ref "D11") (pin "1") (pinfunction "A_1") (pintype "passive"))
      (node (ref "D2") (pin "2") (pinfunction "A_2") (pintype "passive"))
      (node (ref "D3") (pin "2") (pinfunction "A_2") (pintype "passive"))
      (node (ref "D4") (pin "2") (pinfunction "A_2") (pintype "passive"))
      (node (ref "D5") (pin "2") (pinfunction "A_2") (pintype "passive"))
      (node (ref "D6") (pin "2") (pinfunction "A_2") (pintype "passive"))
      (node (ref "D7") (pin "2") (pinfunction "A_2") (pintype "passive"))
      (node (ref "D8") (pin "2") (pinfunction "A_2") (pintype "passive"))
      (node (ref "FM1") (pin "2") (pinfunction "－_2") (pintype "passive"))
      (node (ref "J1") (pin "2") (pinfunction "2_2") (pintype "passive"))
      (node (ref "J10") (pin "2") (pinfunction "2_2") (pintype "passive"))
      (node (ref "J11") (pin "2") (pinfunction "2_2") (pintype "passive"))
      (node (ref "J2") (pin "1") (pinfunction "1_1") (pintype "passive"))
      (node (ref "J3") (pin "1") (pinfunction "1_1") (pintype "passive"))
      (node (ref "J4") (pin "1") (pinfunction "1_1") (pintype "passive"))
      (node (ref "J5") (pin "2") (pinfunction "2_2") (pintype "passive"))
      (node (ref "J6") (pin "1") (pinfunction "1_1") (pintype "passive"))
      (node (ref "J7") (pin "1") (pinfunction "1_1") (pintype "passive"))
      (node (ref "J8") (pin "11") (pinfunction "11_11") (pintype "passive"))
      (node (ref "J9") (pin "2") (pinfunction "2_2") (pintype "passive"))
      (node (ref "JP1") (pin "1") (pinfunction "1_1") (pintype "passive"))
      (node (ref "JP2") (pin "21") (pinfunction "21_21") (pintype "passive"))
      (node (ref "K1") (pin "A") (pinfunction "A_A") (pintype "passive"))
      (node (ref "K2") (pin "A") (pinfunction "A_A") (pintype "passive"))
      (node (ref "K3") (pin "A") (pinfunction "A_A") (pintype "passive"))
      (node (ref "K4") (pin "A") (pinfunction "A_A") (pintype "passive"))
      (node (ref "K5") (pin "A") (pinfunction "A_A") (pintype "passive"))
      (node (ref "P1") (pin "2") (pinfunction "2_2") (pintype "passive"))
      (node (ref "R11") (pin "1") (pinfunction "1_1") (pintype "passive"))
      (node (ref "R12") (pin "1") (pinfunction "1_1") (pintype "passive"))
      (node (ref "R14") (pin "2") (pinfunction "2_2") (pintype "passive"))
      (node (ref "R15") (pin "2") (pinfunction "2_2") (pintype "passive"))
      (node (ref "R22") (pin "1") (pinfunction "1_1") (pintype "passive"))
      (node (ref "R23") (pin "2") (pinfunction "2_2") (pintype "passive"))
      (node (ref "R32") (pin "2") (pinfunction "2_2") (pintype "passive"))
      (node (ref "R37") (pin "1") (pinfunction "1_1") (pintype "passive"))
      (node (ref "SW2") (pin "5") (pinfunction "5_5") (pintype "passive"))
      (node (ref "SW2") (pin "6") (pinfunction "6_6") (pintype "passive"))
      (node (ref "SW2") (pin "7") (pinfunction "7_7") (pintype "passive"))
      (node (ref "SW2") (pin "8") (pinfunction "8_8") (pintype "passive"))
      (node (ref "U1") (pin "4") (pinfunction "GND_4") (pintype "passive"))
      (node (ref "U2") (pin "4") (pinfunction "GND_4") (pintype "passive"))
      (node (ref "U3") (pin "4") (pinfunction "GND_4") (pintype "passive"))
      (node (ref "U4") (pin "1") (pinfunction "GND_1") (pintype "passive"))
      (node (ref "U5") (pin "23") (pinfunction "GND_23") (pintype "passive"))
      (node (ref "U6") (pin "3") (pinfunction "GND_3") (pintype "passive"))
      (node (ref "U6") (pin "5") (pinfunction "ON#/OFF_5") (pintype "passive"))
      (node (ref "U6") (pin "6") (pinfunction "GND_6") (pintype "passive"))
      (node (ref "U7") (pin "1") (pinfunction "GND_1") (pintype "passive"))
      (node (ref "U7") (pin "2") (pinfunction "EN_2") (pintype "passive"))
    )
    (net (code "71") (name "Net-(C17-Pad2)") (class "Default")
      (node (ref "C17") (pin "2") (pinfunction "2_2") (pintype "passive"))
      (node (ref "R37") (pin "2") (pinfunction "2_2") (pintype "passive"))
    )
    (net (code "72") (name "Net-(D9-A)") (class "Default")
      (node (ref "D9") (pin "1") (pinfunction "A_1") (pintype "passive"))
      (node (ref "SW1") (pin "2") (pinfunction "C_2") (pintype "passive"))
    )
    (net (code "73") (name "Net-(D9-C)") (class "Default")
      (node (ref "D9") (pin "2") (pinfunction "C_2") (pintype "passive"))
      (node (ref "F1") (pin "1") (pinfunction "1_1") (pintype "passive"))
    )
    (net (code "74") (name "Net-(D10-PadA)") (class "Default")
      (node (ref "D10") (pin "A") (pinfunction "A_A") (pintype "passive"))
      (node (ref "R29") (pin "1") (pinfunction "1_1") (pintype "passive"))
    )
    (net (code "75") (name "Net-(D11-C)") (class "Default")
      (node (ref "D11") (pin "2") (pinfunction "C_2") (pintype "passive"))
      (node (ref "L1") (pin "2") (pinfunction "2_2") (pintype "passive"))
      (node (ref "U6") (pin "2") (pinfunction "OUTPUT_2") (pintype "passive"))
    )
    (net (code "76") (name "Net-(D12-C)") (class "Default")
      (node (ref "D12") (pin "2") (pinfunction "C_2") (pintype "passive"))
      (node (ref "F3") (pin "2") (pinfunction "2_2") (pintype "passive"))
    )
    (net (code "77") (name "Net-(FM1-+)") (class "Default")
      (node (ref "FM1") (pin "1") (pinfunction "+_1") (pintype "passive"))
      (node (ref "Q1") (pin "3") (pinfunction "C_3") (pintype "passive"))
    )
    (net (code "78") (name "Net-(J5-Pad3)") (class "Default")
      (node (ref "J5") (pin "3") (pinfunction "3_3") (pintype "passive"))
      (node (ref "R16") (pin "2") (pinfunction "2_2") (pintype "passive"))
    )
    (net (code "79") (name "Net-(J5-Pad4)") (class "Default")
      (node (ref "J5") (pin "4") (pinfunction "4_4") (pintype "passive"))
      (node (ref "R13") (pin "2") (pinfunction "2_2") (pintype "passive"))
    )
    (net (code "80") (name "Net-(J6-Pad10)") (class "Default")
      (node (ref "J6") (pin "10") (pinfunction "10_10") (pintype "passive"))
      (node (ref "R17") (pin "1") (pinfunction "1_1") (pintype "passive"))
    )
    (net (code "81") (name "Net-(Q1-B)") (class "Default")
      (node (ref "Q1") (pin "2") (pinfunction "B_2") (pintype "passive"))
      (node (ref "R33") (pin "2") (pinfunction "2_2") (pintype "passive"))
      (node (ref "R34") (pin "2") (pinfunction "2_2") (pintype "passive"))
    )
    (net (code "82") (name "Net-(R30-Pad2)") (class "Default")
      (node (ref "R30") (pin "2") (pinfunction "2_2") (pintype "passive"))
      (node (ref "R31") (pin "1") (pinfunction "1_1") (pintype "passive"))
      (node (ref "R32") (pin "1") (pinfunction "1_1") (pintype "passive"))
    )
    (net (code "83") (name "Net-(U1--IN1)") (class "Default")
      (node (ref "R14") (pin "1") (pinfunction "1_1") (pintype "passive"))
      (node (ref "R7") (pin "3") (pinfunction "3_3") (pintype "passive"))
      (node (ref "U1") (pin "2") (pinfunction "-IN1_2") (pintype "passive"))
    )
    (net (code "84") (name "Net-(U1--IN2)") (class "Default")
      (node (ref "R11") (pin "2") (pinfunction "2_2") (pintype "passive"))
      (node (ref "R9") (pin "1") (pinfunction "1_1") (pintype "passive"))
      (node (ref "U1") (pin "6") (pinfunction "-IN2_6") (pintype "passive"))
    )
    (net (code "85") (name "Net-(U1-OUT1)") (class "Default")
      (node (ref "R1") (pin "2") (pinfunction "2_2") (pintype "passive"))
      (node (ref "R7") (pin "2") (pinfunction "2_2") (pintype "passive"))
      (node (ref "U1") (pin "1") (pinfunction "OUT1_1") (pintype "passive"))
    )
    (net (code "86") (name "Net-(U1-OUT2)") (class "Default")
      (node (ref "R5") (pin "2") (pinfunction "2_2") (pintype "passive"))
      (node (ref "R9") (pin "2") (pinfunction "2_2") (pintype "passive"))
      (node (ref "U1") (pin "7") (pinfunction "OUT2_7") (pintype "passive"))
    )
    (net (code "87") (name "Net-(U2--IN1)") (class "Default")
      (node (ref "R15") (pin "1") (pinfunction "1_1") (pintype "passive"))
      (node (ref "R8") (pin "3") (pinfunction "3_3") (pintype "passive"))
      (node (ref "U2") (pin "2") (pinfunction "-IN1_2") (pintype "passive"))
    )
    (net (code "88") (name "Net-(U2--IN2)") (class "Default")
      (node (ref "R10") (pin "1") (pinfunction "1_1") (pintype "passive"))
      (node (ref "R12") (pin "2") (pinfunction "2_2") (pintype "passive"))
      (node (ref "U2") (pin "6") (pinfunction "-IN2_6") (pintype "passive"))
    )
    (net (code "89") (name "Net-(U2-OUT1)") (class "Default")
      (node (ref "R2") (pin "2") (pinfunction "2_2") (pintype "passive"))
      (node (ref "R8") (pin "2") (pinfunction "2_2") (pintype "passive"))
      (node (ref "U2") (pin "1") (pinfunction "OUT1_1") (pintype "passive"))
    )
    (net (code "90") (name "Net-(U2-OUT2)") (class "Default")
      (node (ref "R10") (pin "2") (pinfunction "2_2") (pintype "passive"))
      (node (ref "R6") (pin "2") (pinfunction "2_2") (pintype "passive"))
      (node (ref "U2") (pin "7") (pinfunction "OUT2_7") (pintype "passive"))
    )
    (net (code "91") (name "Net-(U3--IN1)") (class "Default")
      (node (ref "R20") (pin "3") (pinfunction "3_3") (pintype "passive"))
      (node (ref "R23") (pin "1") (pinfunction "1_1") (pintype "passive"))
      (node (ref "U3") (pin "2") (pinfunction "-IN1_2") (pintype "passive"))
    )
    (net (code "92") (name "Net-(U3--IN2)") (class "Default")
      (node (ref "R21") (pin "1") (pinfunction "1_1") (pintype "passive"))
      (node (ref "R22") (pin "2") (pinfunction "2_2") (pintype "passive"))
      (node (ref "U3") (pin "6") (pinfunction "-IN2_6") (pintype "passive"))
    )
    (net (code "93") (name "Net-(U3-OUT1)") (class "Default")
      (node (ref "R18") (pin "2") (pinfunction "2_2") (pintype "passive"))
      (node (ref "R20") (pin "2") (pinfunction "2_2") (pintype "passive"))
      (node (ref "U3") (pin "1") (pinfunction "OUT1_1") (pintype "passive"))
    )
    (net (code "94") (name "Net-(U3-OUT2)") (class "Default")
      (node (ref "R19") (pin "2") (pinfunction "2_2") (pintype "passive"))
      (node (ref "R21") (pin "2") (pinfunction "2_2") (pintype "passive"))
      (node (ref "U3") (pin "7") (pinfunction "OUT2_7") (pintype "passive"))
    )
    (net (code "95") (name "Net-(U6-FB)") (class "Default")
      (node (ref "C15") (pin "1") (pinfunction "1_1") (pintype "passive"))
      (node (ref "F2") (pin "1") (pinfunction "1_1") (pintype "passive"))
      (node (ref "L1") (pin "1") (pinfunction "1_1") (pintype "passive"))
      (node (ref "U6") (pin "4") (pinfunction "FB_4") (pintype "passive"))
    )
    (net (code "96") (name "Net-(U7-IN)") (class "Default")
      (node (ref "C16") (pin "2") (pinfunction "2_2") (pintype "passive"))
      (node (ref "F3") (pin "1") (pinfunction "1_1") (pintype "passive"))
      (node (ref "U7") (pin "3") (pinfunction "IN/2_3") (pintype "passive"))
      (node (ref "U7") (pin "4") (pinfunction "IN_4") (pintype "passive"))
    )
    (net (code "97") (name "Net-(U7-OUT)") (class "Default")
      (node (ref "C17") (pin "1") (pinfunction "1_1") (pintype "passive"))
      (node (ref "R35") (pin "1") (pinfunction "1_1") (pintype "passive"))
      (node (ref "R36") (pin "2") (pinfunction "2_2") (pintype "passive"))
      (node (ref "U7") (pin "5") (pinfunction "OUT/2_5") (pintype "passive"))
      (node (ref "U7") (pin "6") (pinfunction "OUT_6") (pintype "passive"))
      (node (ref "U7") (pin "7") (pinfunction "SENSEFB_7") (pintype "passive"))
    )
    (net (code "98") (name "Net-(U7-RESET)") (class "Default")
      (node (ref "R36") (pin "1") (pinfunction "1_1") (pintype "passive"))
      (node (ref "U7") (pin "8") (pinfunction "RESET_8") (pintype "passive"))
    )
    (net (code "99") (name "VCC5V_MCU") (class "Default")
      (node (ref "R35") (pin "2") (pinfunction "2_2") (pintype "passive"))
      (node (ref "U5") (pin "24") (pinfunction "5V_24") (pintype "passive"))
    )
    (net (code "100") (name "VCC_3.3V") (class "Default")
      (node (ref "C11") (pin "1") (pinfunction "1_1") (pintype "passive"))
      (node (ref "J1") (pin "1") (pinfunction "1_1") (pintype "passive"))
      (node (ref "J7") (pin "2") (pinfunction "2_2") (pintype "passive"))
      (node (ref "J8") (pin "20") (pinfunction "20_20") (pintype "passive"))
      (node (ref "JP2") (pin "22") (pinfunction "22_22") (pintype "passive"))
      (node (ref "Q1") (pin "1") (pinfunction "E_1") (pintype "passive"))
      (node (ref "R17") (pin "2") (pinfunction "2_2") (pintype "passive"))
      (node (ref "R24") (pin "2") (pinfunction "2_2") (pintype "passive"))
      (node (ref "R25") (pin "2") (pinfunction "2_2") (pintype "passive"))
      (node (ref "R26") (pin "2") (pinfunction "2_2") (pintype "passive"))
      (node (ref "R27") (pin "2") (pinfunction "2_2") (pintype "passive"))
      (node (ref "R28") (pin "2") (pinfunction "2_2") (pintype "passive"))
      (node (ref "R33") (pin "1") (pinfunction "1_1") (pintype "passive"))
      (node (ref "RN1") (pin "5") (pinfunction "5_5") (pintype "passive"))
      (node (ref "RN1") (pin "6") (pinfunction "6_6") (pintype "passive"))
      (node (ref "RN1") (pin "7") (pinfunction "7_7") (pintype "passive"))
      (node (ref "RN1") (pin "8") (pinfunction "8_8") (pintype "passive"))
      (node (ref "U4") (pin "2") (pinfunction "Out_2") (pintype "passive"))
      (node (ref "U4") (pin "4") (pinfunction "TAB_4") (pintype "passive"))
    )
    (net (code "101") (name "VCC_5V") (class "Default")
      (node (ref "C10") (pin "1") (pinfunction "1_1") (pintype "passive"))
      (node (ref "C3") (pin "1") (pinfunction "1_1") (pintype "passive"))
      (node (ref "C4") (pin "1") (pinfunction "1_1") (pintype "passive"))
      (node (ref "C8") (pin "1") (pinfunction "1_1") (pintype "passive"))
      (node (ref "F2") (pin "2") (pinfunction "2_2") (pintype "passive"))
      (node (ref "J3") (pin "6") (pinfunction "6_6") (pintype "passive"))
      (node (ref "J4") (pin "6") (pinfunction "6_6") (pintype "passive"))
      (node (ref "J5") (pin "1") (pinfunction "1_1") (pintype "passive"))
      (node (ref "U1") (pin "8") (pinfunction "VCC+_8") (pintype "passive"))
      (node (ref "U2") (pin "8") (pinfunction "VCC+_8") (pintype "passive"))
      (node (ref "U3") (pin "8") (pinfunction "VCC+_8") (pintype "passive"))
      (node (ref "U4") (pin "3") (pinfunction "In_3") (pintype "passive"))
    )
    (net (code "102") (name "unconnected-(J2-Pad6)") (class "Default")
      (node (ref "J2") (pin "6") (pinfunction "6_6") (pintype "passive"))
    )
    (net (code "103") (name "unconnected-(J3-Pad3)") (class "Default")
      (node (ref "J3") (pin "3") (pinfunction "3_3") (pintype "passive"))
    )
    (net (code "104") (name "unconnected-(J3-Pad4)") (class "Default")
      (node (ref "J3") (pin "4") (pinfunction "4_4") (pintype "passive"))
    )
    (net (code "105") (name "unconnected-(J4-Pad3)") (class "Default")
      (node (ref "J4") (pin "3") (pinfunction "3_3") (pintype "passive"))
    )
    (net (code "106") (name "unconnected-(J4-Pad4)") (class "Default")
      (node (ref "J4") (pin "4") (pinfunction "4_4") (pintype "passive"))
    )
    (net (code "107") (name "unconnected-(J6-Pad3)") (class "Default")
      (node (ref "J6") (pin "3") (pinfunction "3_3") (pintype "passive"))
    )
    (net (code "108") (name "unconnected-(J6-Pad4)") (class "Default")
      (node (ref "J6") (pin "4") (pinfunction "4_4") (pintype "passive"))
    )
    (net (code "109") (name "unconnected-(J6-Pad6)") (class "Default")
      (node (ref "J6") (pin "6") (pinfunction "6_6") (pintype "passive"))
    )
    (net (code "110") (name "unconnected-(J6-Pad19)") (class "Default")
      (node (ref "J6") (pin "19") (pinfunction "19_19") (pintype "passive"))
    )
    (net (code "111") (name "unconnected-(J6-Pad20)") (class "Default")
      (node (ref "J6") (pin "20") (pinfunction "20_20") (pintype "passive"))
    )
    (net (code "112") (name "unconnected-(J8-Pad13)") (class "Default")
      (node (ref "J8") (pin "13") (pinfunction "13_13") (pintype "passive"))
    )
    (net (code "113") (name "unconnected-(J8-Pad14)") (class "Default")
      (node (ref "J8") (pin "14") (pinfunction "14_14") (pintype "passive"))
    )
    (net (code "114") (name "unconnected-(J8-Pad16)") (class "Default")
      (node (ref "J8") (pin "16") (pinfunction "16_16") (pintype "passive"))
    )
    (net (code "115") (name "unconnected-(J8-Pad18)") (class "Default")
      (node (ref "J8") (pin "18") (pinfunction "18_18") (pintype "passive"))
    )
    (net (code "116") (name "unconnected-(J8-Pad19)") (class "Default")
      (node (ref "J8") (pin "19") (pinfunction "19_19") (pintype "passive"))
    )
    (net (code "117") (name "unconnected-(JP1-Pad6)") (class "Default")
      (node (ref "JP1") (pin "6") (pinfunction "6_6") (pintype "passive"))
    )
    (net (code "118") (name "unconnected-(JP2-Pad1)") (class "Default")
      (node (ref "JP2") (pin "1") (pinfunction "1_1") (pintype "passive"))
    )
    (net (code "119") (name "unconnected-(JP2-Pad2)") (class "Default")
      (node (ref "JP2") (pin "2") (pinfunction "2_2") (pintype "passive"))
    )
    (net (code "120") (name "unconnected-(JP2-Pad3)") (class "Default")
      (node (ref "JP2") (pin "3") (pinfunction "3_3") (pintype "passive"))
    )
    (net (code "121") (name "unconnected-(JP2-Pad5)") (class "Default")
      (node (ref "JP2") (pin "5") (pinfunction "5_5") (pintype "passive"))
    )
    (net (code "122") (name "unconnected-(JP2-Pad7)") (class "Default")
      (node (ref "JP2") (pin "7") (pinfunction "7_7") (pintype "passive"))
    )
    (net (code "123") (name "unconnected-(JP2-Pad8)") (class "Default")
      (node (ref "JP2") (pin "8") (pinfunction "8_8") (pintype "passive"))
    )
    (net (code "124") (name "unconnected-(JP2-Pad10)") (class "Default")
      (node (ref "JP2") (pin "10") (pinfunction "10_10") (pintype "passive"))
    )
    (net (code "125") (name "unconnected-(JP2-Pad23)") (class "Default")
      (node (ref "JP2") (pin "23") (pinfunction "23_23") (pintype "passive"))
    )
    (net (code "126") (name "unconnected-(JP2-Pad24)") (class "Default")
      (node (ref "JP2") (pin "24") (pinfunction "24_24") (pintype "passive"))
    )
    (net (code "127") (name "unconnected-(R7-Pad1)") (class "Default")
      (node (ref "R7") (pin "1") (pinfunction "1_1") (pintype "passive"))
    )
    (net (code "128") (name "unconnected-(R8-Pad1)") (class "Default")
      (node (ref "R8") (pin "1") (pinfunction "1_1") (pintype "passive"))
    )
    (net (code "129") (name "unconnected-(R9-Pad3)") (class "Default")
      (node (ref "R9") (pin "3") (pinfunction "3_3") (pintype "passive"))
    )
    (net (code "130") (name "unconnected-(R10-Pad3)") (class "Default")
      (node (ref "R10") (pin "3") (pinfunction "3_3") (pintype "passive"))
    )
    (net (code "131") (name "unconnected-(R20-Pad1)") (class "Default")
      (node (ref "R20") (pin "1") (pinfunction "1_1") (pintype "passive"))
    )
    (net (code "132") (name "unconnected-(R21-Pad3)") (class "Default")
      (node (ref "R21") (pin "3") (pinfunction "3_3") (pintype "passive"))
    )
    (net (code "133") (name "unconnected-(SW1-ON-Pad1)") (class "Default")
      (node (ref "SW1") (pin "1") (pinfunction "ON_1") (pintype "passive"))
    )
    (net (code "134") (name "unconnected-(U5A-C8-Pad4)") (class "Default")
      (node (ref "U5") (pin "4") (pinfunction "C8_4") (pintype "passive"))
    )
    (net (code "135") (name "unconnected-(U5A-C14-Pad10)") (class "Default")
      (node (ref "U5") (pin "10") (pinfunction "C14_10") (pintype "passive"))
    )
    (net (code "136") (name "unconnected-(U5A-C16-Pad12)") (class "Default")
      (node (ref "U5") (pin "12") (pinfunction "C16_12") (pintype "passive"))
    )
    (net (code "137") (name "unconnected-(U5A-C17-Pad14)") (class "Default")
      (node (ref "U5") (pin "14") (pinfunction "C17_14") (pintype "passive"))
    )
    (net (code "138") (name "unconnected-(U5A-C18-Pad16)") (class "Default")
      (node (ref "U5") (pin "16") (pinfunction "C18_16") (pintype "passive"))
    )
    (net (code "139") (name "unconnected-(U5A-C19-Pad13)") (class "Default")
      (node (ref "U5") (pin "13") (pinfunction "C19_13") (pintype "passive"))
    )
    (net (code "140") (name "unconnected-(U5A-D0-Pad15)") (class "Default")
      (node (ref "U5") (pin "15") (pinfunction "D0_15") (pintype "passive"))
    )
    (net (code "141") (name "unconnected-(U5A-D1-Pad17)") (class "Default")
      (node (ref "U5") (pin "17") (pinfunction "D1_17") (pintype "passive"))
    )
    (net (code "142") (name "unconnected-(U5B-0DM0-Pad53)") (class "Default")
      (node (ref "U5") (pin "53") (pinfunction "0DM0_53") (pintype "passive"))
    )
    (net (code "143") (name "unconnected-(U5B-0DM1-Pad49)") (class "Default")
      (node (ref "U5") (pin "49") (pinfunction "0DM1_49") (pintype "passive"))
    )
    (net (code "144") (name "unconnected-(U5B-0DP0-Pad54)") (class "Default")
      (node (ref "U5") (pin "54") (pinfunction "0DP0_54") (pintype "passive"))
    )
    (net (code "145") (name "unconnected-(U5B-0DP1-Pad50)") (class "Default")
      (node (ref "U5") (pin "50") (pinfunction "0DP1_50") (pintype "passive"))
    )
    (net (code "146") (name "unconnected-(U5B-1DM1-Pad51)") (class "Default")
      (node (ref "U5") (pin "51") (pinfunction "1DM1_51") (pintype "passive"))
    )
    (net (code "147") (name "unconnected-(U5B-1DP1-Pad52)") (class "Default")
      (node (ref "U5") (pin "52") (pinfunction "1DP1_52") (pintype "passive"))
    )
    (net (code "148") (name "unconnected-(U5B-D12-Pad30)") (class "Default")
      (node (ref "U5") (pin "30") (pinfunction "D12_30") (pintype "passive"))
    )
    (net (code "149") (name "unconnected-(U5B-D14-Pad32)") (class "Default")
      (node (ref "U5") (pin "32") (pinfunction "D14_32") (pintype "passive"))
    )
    (net (code "150") (name "unconnected-(U5B-E0-Pad34)") (class "Default")
      (node (ref "U5") (pin "34") (pinfunction "E0_34") (pintype "passive"))
    )
    (net (code "151") (name "unconnected-(U5B-E2-Pad36)") (class "Default")
      (node (ref "U5") (pin "36") (pinfunction "E2_36") (pintype "passive"))
    )
    (net (code "152") (name "unconnected-(U5B-E6-Pad40)") (class "Default")
      (node (ref "U5") (pin "40") (pinfunction "E6_40") (pintype "passive"))
    )
    (net (code "153") (name "unconnected-(U5B-E7-Pad42)") (class "Default")
      (node (ref "U5") (pin "42") (pinfunction "E7_42") (pintype "passive"))
    )
    (net (code "154") (name "unconnected-(U5B-UDM-Pad47)") (class "Default")
      (node (ref "U5") (pin "47") (pinfunction "UDM_47") (pintype "passive"))
    )
    (net (code "155") (name "unconnected-(U5B-UDP-Pad48)") (class "Default")
      (node (ref "U5") (pin "48") (pinfunction "UDP_48") (pintype "passive"))
    )
    (net (code "156") (name "unconnected-(U5C-0S16-Pad78)") (class "Default")
      (node (ref "U5") (pin "78") (pinfunction "0S16_78") (pintype "passive"))
    )
    (net (code "157") (name "unconnected-(U5C-1S16-Pad77)") (class "Default")
      (node (ref "U5") (pin "77") (pinfunction "1S16_77") (pintype "passive"))
    )
    (net (code "158") (name "unconnected-(U5C-3.3V-Pad80)") (class "Default")
      (node (ref "U5") (pin "80") (pinfunction "3.3V_80") (pintype "passive+no_connect"))
    )
    (net (code "159") (name "unconnected-(U5C-A5-Pad69)") (class "Default")
      (node (ref "U5") (pin "69") (pinfunction "A5_69") (pintype "passive"))
    )
    (net (code "160") (name "unconnected-(U5C-A6-Pad68)") (class "Default")
      (node (ref "U5") (pin "68") (pinfunction "A6_68") (pintype "passive"))
    )
    (net (code "161") (name "unconnected-(U5C-A12-Pad62)") (class "Default")
      (node (ref "U5") (pin "62") (pinfunction "A12_62") (pintype "passive"))
    )
    (net (code "162") (name "unconnected-(U5C-A13-Pad61)") (class "Default")
      (node (ref "U5") (pin "61") (pinfunction "A13_61") (pintype "passive"))
    )
    (net (code "163") (name "unconnected-(U5C-A14-Pad60)") (class "Default")
      (node (ref "U5") (pin "60") (pinfunction "A14_60") (pintype "passive"))
    )
    (net (code "164") (name "unconnected-(U5C-A15-Pad59)") (class "Default")
      (node (ref "U5") (pin "59") (pinfunction "A15_59") (pintype "passive"))
    )
    (net (code "165") (name "unconnected-(U5C-A16-Pad58)") (class "Default")
      (node (ref "U5") (pin "58") (pinfunction "A16_58") (pintype "passive"))
    )
    (net (code "166") (name "unconnected-(U5C-DA0-Pad76)") (class "Default")
      (node (ref "U5") (pin "76") (pinfunction "DA0_76") (pintype "passive"))
    )
    (net (code "167") (name "unconnected-(U5C-DA1-Pad75)") (class "Default")
      (node (ref "U5") (pin "75") (pinfunction "DA1_75") (pintype "passive"))
    )
    (net (code "168") (name "unconnected-(U5C-E26-Pad72)") (class "Default")
      (node (ref "U5") (pin "72") (pinfunction "E26_72") (pintype "passive+no_connect"))
    )
    (net (code "169") (name "unconnected-(U5C-E27-Pad71)") (class "Default")
      (node (ref "U5") (pin "71") (pinfunction "E27_71") (pintype "passive+no_connect"))
    )
    (net (code "170") (name "unconnected-(U5C-E28-Pad70)") (class "Default")
      (node (ref "U5") (pin "70") (pinfunction "E28_70") (pintype "passive"))
    )
    (net (code "171") (name "unconnected-(U5C-REF-Pad79)") (class "Default")
      (node (ref "U5") (pin "79") (pinfunction "REF_79") (pintype "passive+no_connect"))
    )
    (net (code "172") (name "unconnected-(U5D-A19-Pad111)") (class "Default")
      (node (ref "U5") (pin "111") (pinfunction "A19_111") (pintype "passive"))
    )
    (net (code "173") (name "unconnected-(U5D-A24-Pad109)") (class "Default")
      (node (ref "U5") (pin "109") (pinfunction "A24_109") (pintype "passive"))
    )
    (net (code "174") (name "unconnected-(U5D-B8-Pad97)") (class "Default")
      (node (ref "U5") (pin "97") (pinfunction "B8_97") (pintype "passive"))
    )
    (net (code "175") (name "unconnected-(U5D-B9-Pad96)") (class "Default")
      (node (ref "U5") (pin "96") (pinfunction "B9_96") (pintype "passive+no_connect"))
    )
    (net (code "176") (name "unconnected-(U5D-B11-Pad95)") (class "Default")
      (node (ref "U5") (pin "95") (pinfunction "B11_95") (pintype "passive+no_connect"))
    )
    (net (code "177") (name "unconnected-(U5D-B16-Pad92)") (class "Default")
      (node (ref "U5") (pin "92") (pinfunction "B16_92") (pintype "passive"))
    )
    (net (code "178") (name "unconnected-(U5D-B17-Pad93)") (class "Default")
      (node (ref "U5") (pin "93") (pinfunction "B17_93") (pintype "passive"))
    )
    (net (code "179") (name "unconnected-(U5D-B18-Pad90)") (class "Default")
      (node (ref "U5") (pin "90") (pinfunction "B18_90") (pintype "passive"))
    )
    (net (code "180") (name "unconnected-(U5D-B19-Pad91)") (class "Default")
      (node (ref "U5") (pin "91") (pinfunction "B19_91") (pintype "passive"))
    )
    (net (code "181") (name "unconnected-(U5D-B20-Pad88)") (class "Default")
      (node (ref "U5") (pin "88") (pinfunction "B20_88") (pintype "passive"))
    )
    (net (code "182") (name "unconnected-(U5D-B21-Pad89)") (class "Default")
      (node (ref "U5") (pin "89") (pinfunction "B21_89") (pintype "passive"))
    )
    (net (code "183") (name "unconnected-(U5D-B22-Pad86)") (class "Default")
      (node (ref "U5") (pin "86") (pinfunction "B22_86") (pintype "passive"))
    )
    (net (code "184") (name "unconnected-(U5D-B23-Pad87)") (class "Default")
      (node (ref "U5") (pin "87") (pinfunction "B23_87") (pintype "passive"))
    )
  )
)
